# octanis_eps_mcu_shdn.net
KiCad netlist of a schematic drawn in EAGLE
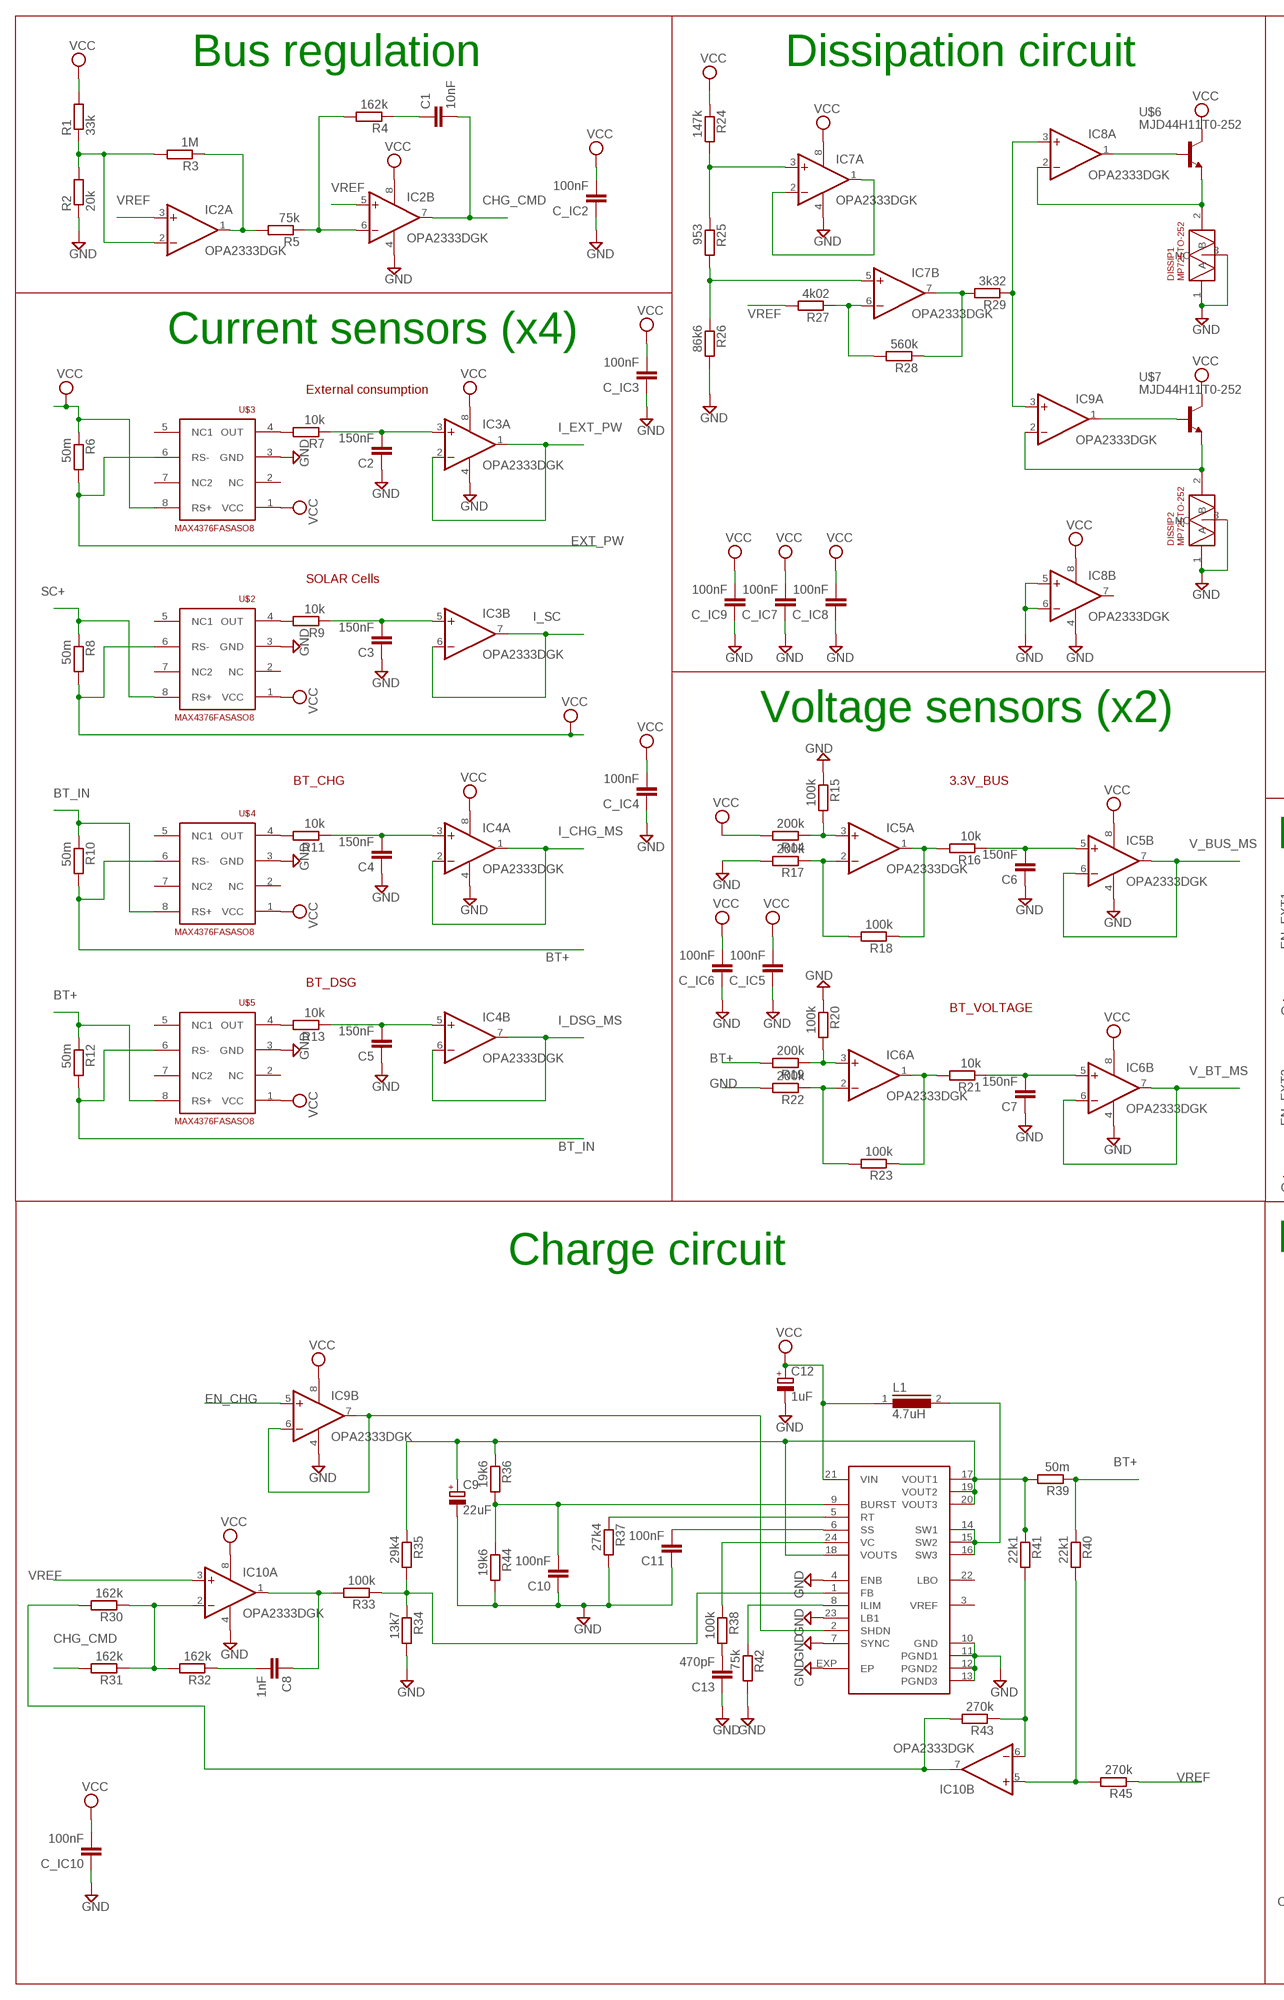
[diagram p0: schematic, sheet 1, part 1 of 2]
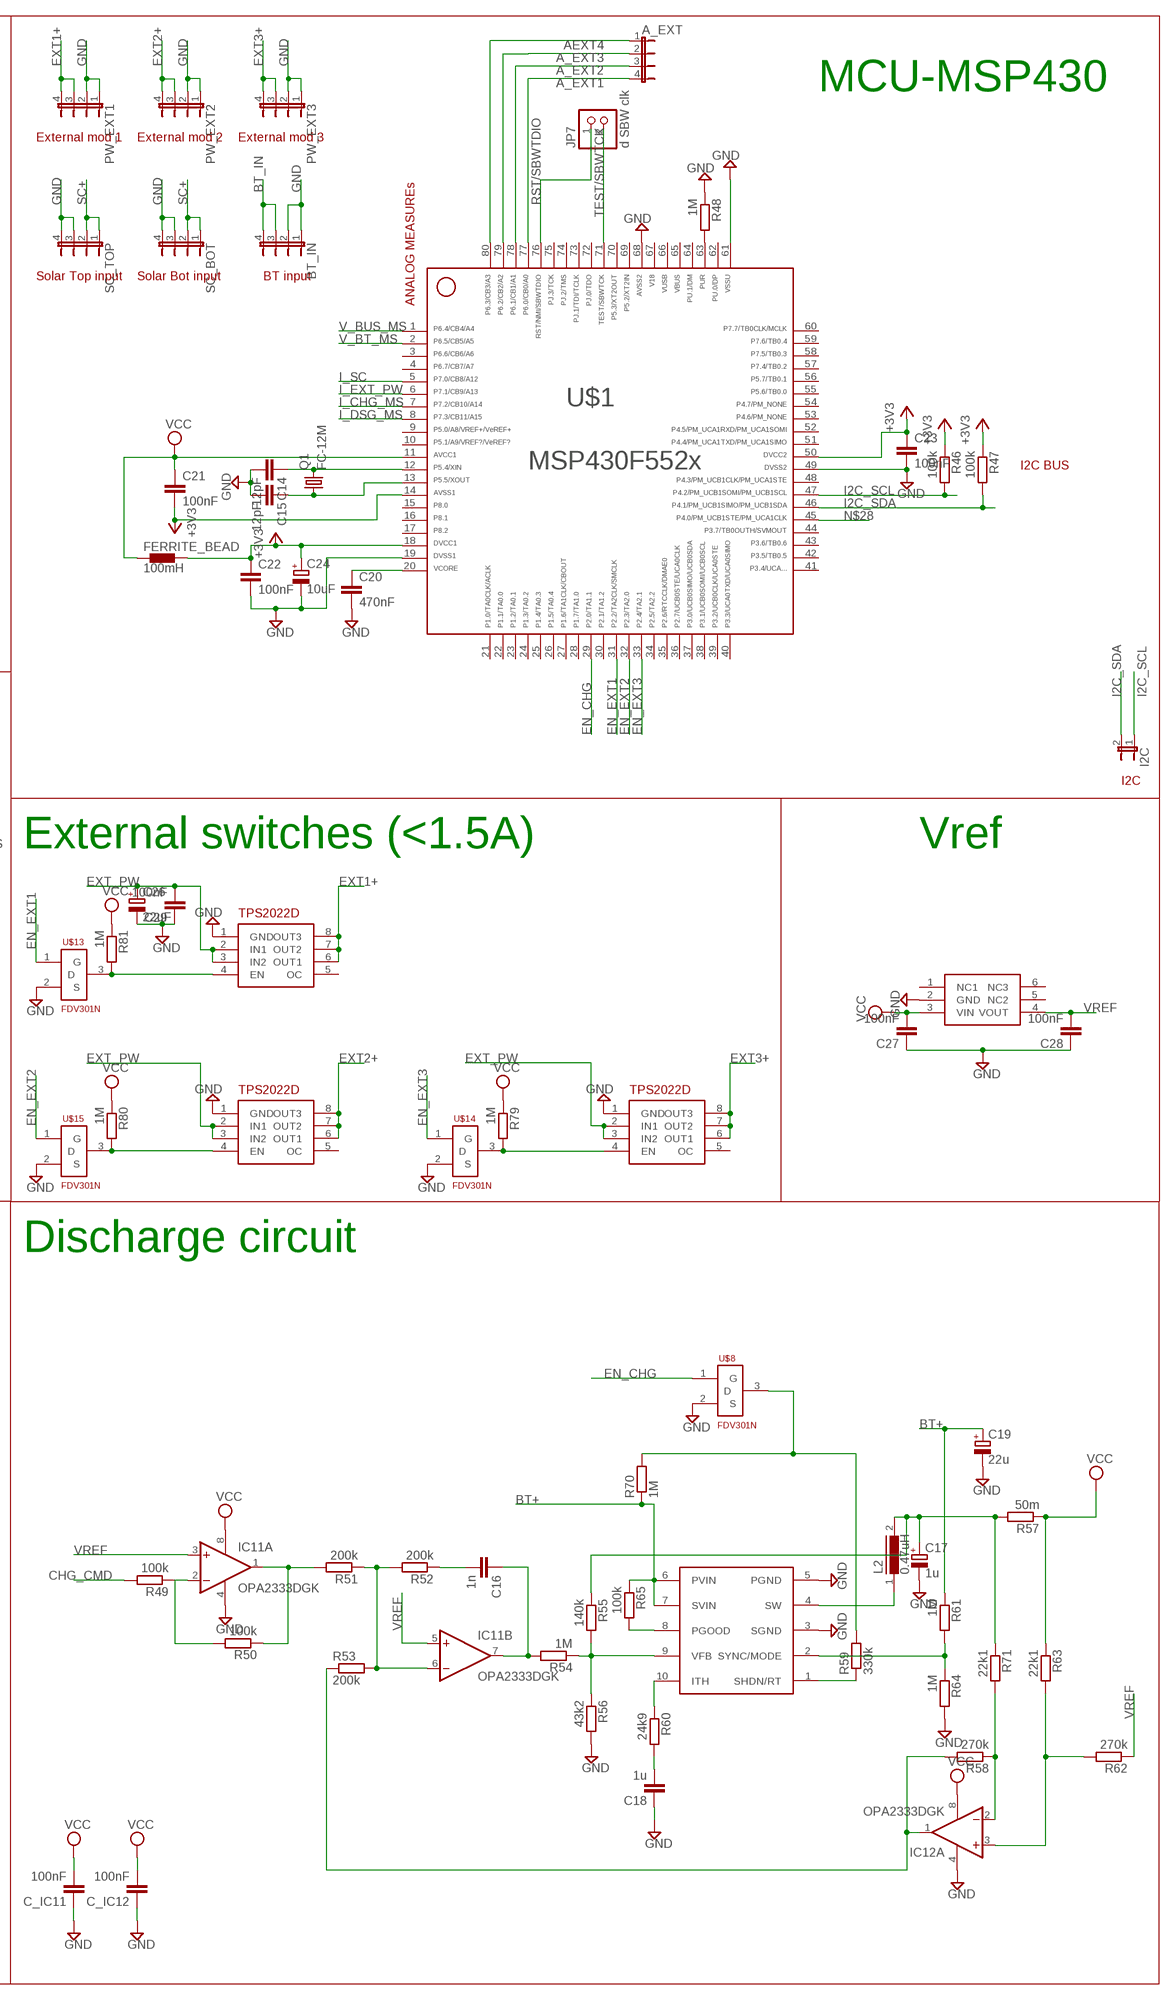
[diagram p1: schematic, sheet 1, part 2 of 2]

(export (version "E")
  (design (tool "Eeschema 10.0.6"))
  (components
    (comp (ref "A_EXT")
      (value "JP4E")
      (footprint "eagle-import:JP4")
      (libsource (lib "eagle-import") (part "JP4E"))
    )
    (comp (ref "BT_IN")
      (value "JP4E")
      (footprint "eagle-import:JP4")
      (libsource (lib "eagle-import") (part "JP4E"))
    )
    (comp (ref "C1")
      (value "10nF")
      (footprint "eagle-import:C0603")
      (libsource (lib "eagle-import") (part "C-EUC0603"))
    )
    (comp (ref "C2")
      (value "150nF")
      (footprint "eagle-import:C0603")
      (libsource (lib "eagle-import") (part "C-EUC0603"))
    )
    (comp (ref "C3")
      (value "150nF")
      (footprint "eagle-import:C0603")
      (libsource (lib "eagle-import") (part "C-EUC0603"))
    )
    (comp (ref "C4")
      (value "150nF")
      (footprint "eagle-import:C0603")
      (libsource (lib "eagle-import") (part "C-EUC0603"))
    )
    (comp (ref "C5")
      (value "150nF")
      (footprint "eagle-import:C0603")
      (libsource (lib "eagle-import") (part "C-EUC0603"))
    )
    (comp (ref "C6")
      (value "150nF")
      (footprint "eagle-import:C0603")
      (libsource (lib "eagle-import") (part "C-EUC0603"))
    )
    (comp (ref "C7")
      (value "150nF")
      (footprint "eagle-import:C0603")
      (libsource (lib "eagle-import") (part "C-EUC0603"))
    )
    (comp (ref "C8")
      (value "1nF")
      (footprint "eagle-import:C0603")
      (libsource (lib "eagle-import") (part "C-EUC0603"))
    )
    (comp (ref "C9")
      (value "22uF")
      (footprint "eagle-import:A_3216-18R")
      (libsource (lib "eagle-import") (part "CPOL-EUA/3216-18R"))
    )
    (comp (ref "C10")
      (value "100nF")
      (footprint "eagle-import:C0603")
      (libsource (lib "eagle-import") (part "C-EUC0603"))
    )
    (comp (ref "C11")
      (value "100nF")
      (footprint "eagle-import:C0603")
      (libsource (lib "eagle-import") (part "C-EUC0603"))
    )
    (comp (ref "C12")
      (value "1uF")
      (footprint "eagle-import:A_3216-18R")
      (libsource (lib "eagle-import") (part "CPOL-EUA/3216-18R"))
    )
    (comp (ref "C13")
      (value "470pF")
      (footprint "eagle-import:C0603")
      (libsource (lib "eagle-import") (part "C-EUC0603"))
    )
    (comp (ref "C14")
      (value "12pF")
      (footprint "eagle-import:C0603")
      (libsource (lib "eagle-import") (part "C-EUC0603"))
    )
    (comp (ref "C15")
      (value "12pF")
      (footprint "eagle-import:C0603")
      (libsource (lib "eagle-import") (part "C-EUC0603"))
    )
    (comp (ref "C16")
      (value "1n")
      (footprint "eagle-import:C0603")
      (libsource (lib "eagle-import") (part "C-EUC0603"))
    )
    (comp (ref "C17")
      (value "1u")
      (footprint "eagle-import:A_3216-18R")
      (libsource (lib "eagle-import") (part "CPOL-EUA/3216-18R"))
    )
    (comp (ref "C18")
      (value "1u")
      (footprint "eagle-import:C0603")
      (libsource (lib "eagle-import") (part "C-EUC0603"))
    )
    (comp (ref "C19")
      (value "22u")
      (footprint "eagle-import:A_3216-18R")
      (libsource (lib "eagle-import") (part "CPOL-EUA/3216-18R"))
    )
    (comp (ref "C20")
      (value "470nF")
      (footprint "eagle-import:C0603")
      (libsource (lib "eagle-import") (part "C-EUC0603"))
    )
    (comp (ref "C21")
      (value "100nF")
      (footprint "eagle-import:C0603")
      (libsource (lib "eagle-import") (part "C-EUC0603"))
    )
    (comp (ref "C22")
      (value "100nF")
      (footprint "eagle-import:C0603")
      (libsource (lib "eagle-import") (part "C-EUC0603"))
    )
    (comp (ref "C23")
      (value "100nF")
      (footprint "eagle-import:C0603")
      (libsource (lib "eagle-import") (part "C-EUC0603"))
    )
    (comp (ref "C24")
      (value "10uF")
      (footprint "eagle-import:A_3216-18R")
      (libsource (lib "eagle-import") (part "CPOL-EUA/3216-18R"))
    )
    (comp (ref "C26")
      (value "22uF")
      (footprint "eagle-import:A_3216-18R")
      (libsource (lib "eagle-import") (part "CPOL-EUA/3216-18R"))
    )
    (comp (ref "C27")
      (value "100nF")
      (footprint "eagle-import:C0603")
      (libsource (lib "eagle-import") (part "C-EUC0603"))
    )
    (comp (ref "C28")
      (value "100nF")
      (footprint "eagle-import:C0603")
      (libsource (lib "eagle-import") (part "C-EUC0603"))
    )
    (comp (ref "C29")
      (value "100nF")
      (footprint "eagle-import:C0603")
      (libsource (lib "eagle-import") (part "C-EUC0603"))
    )
    (comp (ref "C_IC2")
      (value "100nF")
      (footprint "eagle-import:C0603")
      (libsource (lib "eagle-import") (part "C-EUC0603"))
    )
    (comp (ref "C_IC3")
      (value "100nF")
      (footprint "eagle-import:C0603")
      (libsource (lib "eagle-import") (part "C-EUC0603"))
    )
    (comp (ref "C_IC4")
      (value "100nF")
      (footprint "eagle-import:C0603")
      (libsource (lib "eagle-import") (part "C-EUC0603"))
    )
    (comp (ref "C_IC5")
      (value "100nF")
      (footprint "eagle-import:C0603")
      (libsource (lib "eagle-import") (part "C-EUC0603"))
    )
    (comp (ref "C_IC6")
      (value "100nF")
      (footprint "eagle-import:C0603")
      (libsource (lib "eagle-import") (part "C-EUC0603"))
    )
    (comp (ref "C_IC7")
      (value "100nF")
      (footprint "eagle-import:C0603")
      (libsource (lib "eagle-import") (part "C-EUC0603"))
    )
    (comp (ref "C_IC8")
      (value "100nF")
      (footprint "eagle-import:C0603")
      (libsource (lib "eagle-import") (part "C-EUC0603"))
    )
    (comp (ref "C_IC9")
      (value "100nF")
      (footprint "eagle-import:C0603")
      (libsource (lib "eagle-import") (part "C-EUC0603"))
    )
    (comp (ref "C_IC10")
      (value "100nF")
      (footprint "eagle-import:C0603")
      (libsource (lib "eagle-import") (part "C-EUC0603"))
    )
    (comp (ref "C_IC11")
      (value "100nF")
      (footprint "eagle-import:C0603")
      (libsource (lib "eagle-import") (part "C-EUC0603"))
    )
    (comp (ref "C_IC12")
      (value "100nF")
      (footprint "eagle-import:C0603")
      (libsource (lib "eagle-import") (part "C-EUC0603"))
    )
    (comp (ref "DISSIP1")
      (value "MP725TO-252")
      (footprint "eagle-import:TO252")
      (libsource (lib "eagle-import") (part "MP725TO-252"))
    )
    (comp (ref "DISSIP2")
      (value "MP725TO-252")
      (footprint "eagle-import:TO252")
      (libsource (lib "eagle-import") (part "MP725TO-252"))
    )
    (comp (ref "FERRITE_BEAD")
      (value "100mH")
      (footprint "eagle-import:0402")
      (libsource (lib "eagle-import") (part "BLM15HD601SN1"))
    )
    (comp (ref "I2C")
      (value "JP1E")
      (footprint "eagle-import:JP1")
      (libsource (lib "eagle-import") (part "JP1E"))
    )
    (comp (ref "IC2")
      (value "OPA2333DGK")
      (footprint "eagle-import:MSOP08")
      (libsource (lib "eagle-import") (part "OPA2333DGK"))
    )
    (comp (ref "IC3")
      (value "OPA2333DGK")
      (footprint "eagle-import:MSOP08")
      (libsource (lib "eagle-import") (part "OPA2333DGK"))
    )
    (comp (ref "IC4")
      (value "OPA2333DGK")
      (footprint "eagle-import:MSOP08")
      (libsource (lib "eagle-import") (part "OPA2333DGK"))
    )
    (comp (ref "IC5")
      (value "OPA2333DGK")
      (footprint "eagle-import:MSOP08")
      (libsource (lib "eagle-import") (part "OPA2333DGK"))
    )
    (comp (ref "IC6")
      (value "OPA2333DGK")
      (footprint "eagle-import:MSOP08")
      (libsource (lib "eagle-import") (part "OPA2333DGK"))
    )
    (comp (ref "IC7")
      (value "OPA2333DGK")
      (footprint "eagle-import:MSOP08")
      (libsource (lib "eagle-import") (part "OPA2333DGK"))
    )
    (comp (ref "IC8")
      (value "OPA2333DGK")
      (footprint "eagle-import:MSOP08")
      (libsource (lib "eagle-import") (part "OPA2333DGK"))
    )
    (comp (ref "IC9")
      (value "OPA2333DGK")
      (footprint "eagle-import:MSOP08")
      (libsource (lib "eagle-import") (part "OPA2333DGK"))
    )
    (comp (ref "IC10")
      (value "OPA2333DGK")
      (footprint "eagle-import:MSOP08")
      (libsource (lib "eagle-import") (part "OPA2333DGK"))
    )
    (comp (ref "IC11")
      (value "OPA2333DGK")
      (footprint "eagle-import:MSOP08")
      (libsource (lib "eagle-import") (part "OPA2333DGK"))
    )
    (comp (ref "IC12")
      (value "OPA2333DGK")
      (footprint "eagle-import:MSOP08")
      (libsource (lib "eagle-import") (part "OPA2333DGK"))
    )
    (comp (ref "JP7")
      (value "d SBW clk")
      (footprint "eagle-import:1X02")
      (libsource (lib "eagle-import") (part "PINHD-1X2"))
    )
    (comp (ref "L1")
      (value "4.7uH")
      (footprint "eagle-import:DR73")
      (libsource (lib "eagle-import") (part "DR73"))
    )
    (comp (ref "L2")
      (value "0.47uH")
      (footprint "eagle-import:DR73")
      (libsource (lib "eagle-import") (part "DR73"))
    )
    (comp (ref "LTC3411")
      (value "LT3411")
      (footprint "eagle-import:MSOP10")
      (libsource (lib "eagle-import") (part "LT3411"))
    )
    (comp (ref "PW_EXT1")
      (value "JP4E")
      (footprint "eagle-import:JP4")
      (libsource (lib "eagle-import") (part "JP4E"))
    )
    (comp (ref "PW_EXT2")
      (value "JP4E")
      (footprint "eagle-import:JP4")
      (libsource (lib "eagle-import") (part "JP4E"))
    )
    (comp (ref "PW_EXT3")
      (value "JP4E")
      (footprint "eagle-import:JP4")
      (libsource (lib "eagle-import") (part "JP4E"))
    )
    (comp (ref "Q1")
      (value "FC-12M")
      (footprint "eagle-import:FC-12M")
      (libsource (lib "eagle-import") (part "FC-12M"))
    )
    (comp (ref "R1")
      (value "33k")
      (footprint "eagle-import:R0603")
      (libsource (lib "eagle-import") (part "R-EU_R0603"))
    )
    (comp (ref "R2")
      (value "20k")
      (footprint "eagle-import:R0603")
      (libsource (lib "eagle-import") (part "R-EU_R0603"))
    )
    (comp (ref "R3")
      (value "1M")
      (footprint "eagle-import:R0603")
      (libsource (lib "eagle-import") (part "R-EU_R0603"))
    )
    (comp (ref "R4")
      (value "162k")
      (footprint "eagle-import:R0603")
      (libsource (lib "eagle-import") (part "R-EU_R0603"))
    )
    (comp (ref "R5")
      (value "75k")
      (footprint "eagle-import:R0603")
      (libsource (lib "eagle-import") (part "R-EU_R0603"))
    )
    (comp (ref "R6")
      (value "50m")
      (footprint "eagle-import:R1206")
      (libsource (lib "eagle-import") (part "R-EU_R1206"))
    )
    (comp (ref "R7")
      (value "10k")
      (footprint "eagle-import:R0603")
      (libsource (lib "eagle-import") (part "R-EU_R0603"))
    )
    (comp (ref "R8")
      (value "50m")
      (footprint "eagle-import:R1206")
      (libsource (lib "eagle-import") (part "R-EU_R1206"))
    )
    (comp (ref "R9")
      (value "10k")
      (footprint "eagle-import:R0603")
      (libsource (lib "eagle-import") (part "R-EU_R0603"))
    )
    (comp (ref "R10")
      (value "50m")
      (footprint "eagle-import:R1206")
      (libsource (lib "eagle-import") (part "R-EU_R1206"))
    )
    (comp (ref "R11")
      (value "10k")
      (footprint "eagle-import:R0603")
      (libsource (lib "eagle-import") (part "R-EU_R0603"))
    )
    (comp (ref "R12")
      (value "50m")
      (footprint "eagle-import:R1206")
      (libsource (lib "eagle-import") (part "R-EU_R1206"))
    )
    (comp (ref "R13")
      (value "10k")
      (footprint "eagle-import:R0603")
      (libsource (lib "eagle-import") (part "R-EU_R0603"))
    )
    (comp (ref "R14")
      (value "200k")
      (footprint "eagle-import:R0603")
      (libsource (lib "eagle-import") (part "R-EU_R0603"))
    )
    (comp (ref "R15")
      (value "100k")
      (footprint "eagle-import:R0603")
      (libsource (lib "eagle-import") (part "R-EU_R0603"))
    )
    (comp (ref "R16")
      (value "10k")
      (footprint "eagle-import:R0603")
      (libsource (lib "eagle-import") (part "R-EU_R0603"))
    )
    (comp (ref "R17")
      (value "200k")
      (footprint "eagle-import:R0603")
      (libsource (lib "eagle-import") (part "R-EU_R0603"))
    )
    (comp (ref "R18")
      (value "100k")
      (footprint "eagle-import:R0603")
      (libsource (lib "eagle-import") (part "R-EU_R0603"))
    )
    (comp (ref "R19")
      (value "200k")
      (footprint "eagle-import:R0603")
      (libsource (lib "eagle-import") (part "R-EU_R0603"))
    )
    (comp (ref "R20")
      (value "100k")
      (footprint "eagle-import:R0603")
      (libsource (lib "eagle-import") (part "R-EU_R0603"))
    )
    (comp (ref "R21")
      (value "10k")
      (footprint "eagle-import:R0603")
      (libsource (lib "eagle-import") (part "R-EU_R0603"))
    )
    (comp (ref "R22")
      (value "200k")
      (footprint "eagle-import:R0603")
      (libsource (lib "eagle-import") (part "R-EU_R0603"))
    )
    (comp (ref "R23")
      (value "100k")
      (footprint "eagle-import:R0603")
      (libsource (lib "eagle-import") (part "R-EU_R0603"))
    )
    (comp (ref "R24")
      (value "147k")
      (footprint "eagle-import:R0603")
      (libsource (lib "eagle-import") (part "R-EU_R0603"))
    )
    (comp (ref "R25")
      (value "953")
      (footprint "eagle-import:R0603")
      (libsource (lib "eagle-import") (part "R-EU_R0603"))
    )
    (comp (ref "R26")
      (value "86k6")
      (footprint "eagle-import:R0603")
      (libsource (lib "eagle-import") (part "R-EU_R0603"))
    )
    (comp (ref "R27")
      (value "4k02")
      (footprint "eagle-import:R0603")
      (libsource (lib "eagle-import") (part "R-EU_R0603"))
    )
    (comp (ref "R28")
      (value "560k")
      (footprint "eagle-import:R0603")
      (libsource (lib "eagle-import") (part "R-EU_R0603"))
    )
    (comp (ref "R29")
      (value "3k32")
      (footprint "eagle-import:R0603")
      (libsource (lib "eagle-import") (part "R-EU_R0603"))
    )
    (comp (ref "R30")
      (value "162k")
      (footprint "eagle-import:R0603")
      (libsource (lib "eagle-import") (part "R-EU_R0603"))
    )
    (comp (ref "R31")
      (value "162k")
      (footprint "eagle-import:R0603")
      (libsource (lib "eagle-import") (part "R-EU_R0603"))
    )
    (comp (ref "R32")
      (value "162k")
      (footprint "eagle-import:R0603")
      (libsource (lib "eagle-import") (part "R-EU_R0603"))
    )
    (comp (ref "R33")
      (value "100k")
      (footprint "eagle-import:R0603")
      (libsource (lib "eagle-import") (part "R-EU_R0603"))
    )
    (comp (ref "R34")
      (value "13k7")
      (footprint "eagle-import:R0603")
      (libsource (lib "eagle-import") (part "R-EU_R0603"))
    )
    (comp (ref "R35")
      (value "29k4")
      (footprint "eagle-import:R0603")
      (libsource (lib "eagle-import") (part "R-EU_R0603"))
    )
    (comp (ref "R36")
      (value "19k6")
      (footprint "eagle-import:R0603")
      (libsource (lib "eagle-import") (part "R-EU_R0603"))
    )
    (comp (ref "R37")
      (value "27k4")
      (footprint "eagle-import:R0603")
      (libsource (lib "eagle-import") (part "R-EU_R0603"))
    )
    (comp (ref "R38")
      (value "100k")
      (footprint "eagle-import:R0603")
      (libsource (lib "eagle-import") (part "R-EU_R0603"))
    )
    (comp (ref "R39")
      (value "50m")
      (footprint "eagle-import:R1206")
      (libsource (lib "eagle-import") (part "R-EU_R1206"))
    )
    (comp (ref "R40")
      (value "22k1")
      (footprint "eagle-import:R0603")
      (libsource (lib "eagle-import") (part "R-EU_R0603"))
    )
    (comp (ref "R41")
      (value "22k1")
      (footprint "eagle-import:R0603")
      (libsource (lib "eagle-import") (part "R-EU_R0603"))
    )
    (comp (ref "R42")
      (value "75k")
      (footprint "eagle-import:R0603")
      (libsource (lib "eagle-import") (part "R-EU_R0603"))
    )
    (comp (ref "R43")
      (value "270k")
      (footprint "eagle-import:R0603")
      (libsource (lib "eagle-import") (part "R-EU_R0603"))
    )
    (comp (ref "R44")
      (value "19k6")
      (footprint "eagle-import:R0603")
      (libsource (lib "eagle-import") (part "R-EU_R0603"))
    )
    (comp (ref "R45")
      (value "270k")
      (footprint "eagle-import:R0603")
      (libsource (lib "eagle-import") (part "R-EU_R0603"))
    )
    (comp (ref "R46")
      (value "100k")
      (footprint "eagle-import:R0603")
      (libsource (lib "eagle-import") (part "R-EU_R0603"))
    )
    (comp (ref "R47")
      (value "100k")
      (footprint "eagle-import:R0603")
      (libsource (lib "eagle-import") (part "R-EU_R0603"))
    )
    (comp (ref "R48")
      (value "1M")
      (footprint "eagle-import:R0603")
      (libsource (lib "eagle-import") (part "R-EU_R0603"))
    )
    (comp (ref "R49")
      (value "100k")
      (footprint "eagle-import:R0603")
      (libsource (lib "eagle-import") (part "R-EU_R0603"))
    )
    (comp (ref "R50")
      (value "100k")
      (footprint "eagle-import:R0603")
      (libsource (lib "eagle-import") (part "R-EU_R0603"))
    )
    (comp (ref "R51")
      (value "200k")
      (footprint "eagle-import:R0603")
      (libsource (lib "eagle-import") (part "R-EU_R0603"))
    )
    (comp (ref "R52")
      (value "200k")
      (footprint "eagle-import:R0603")
      (libsource (lib "eagle-import") (part "R-EU_R0603"))
    )
    (comp (ref "R53")
      (value "200k")
      (footprint "eagle-import:R0603")
      (libsource (lib "eagle-import") (part "R-EU_R0603"))
    )
    (comp (ref "R54")
      (value "1M")
      (footprint "eagle-import:R0603")
      (libsource (lib "eagle-import") (part "R-EU_R0603"))
    )
    (comp (ref "R55")
      (value "140k")
      (footprint "eagle-import:R0603")
      (libsource (lib "eagle-import") (part "R-EU_R0603"))
    )
    (comp (ref "R56")
      (value "43k2")
      (footprint "eagle-import:R0603")
      (libsource (lib "eagle-import") (part "R-EU_R0603"))
    )
    (comp (ref "R57")
      (value "50m")
      (footprint "eagle-import:R1206")
      (libsource (lib "eagle-import") (part "R-EU_R1206"))
    )
    (comp (ref "R58")
      (value "270k")
      (footprint "eagle-import:R0603")
      (libsource (lib "eagle-import") (part "R-EU_R0603"))
    )
    (comp (ref "R59")
      (value "330k")
      (footprint "eagle-import:R0603")
      (libsource (lib "eagle-import") (part "R-EU_R0603"))
    )
    (comp (ref "R60")
      (value "24k9")
      (footprint "eagle-import:R0603")
      (libsource (lib "eagle-import") (part "R-EU_R0603"))
    )
    (comp (ref "R61")
      (value "1M")
      (footprint "eagle-import:R0603")
      (libsource (lib "eagle-import") (part "R-EU_R0603"))
    )
    (comp (ref "R62")
      (value "270k")
      (footprint "eagle-import:R0603")
      (libsource (lib "eagle-import") (part "R-EU_R0603"))
    )
    (comp (ref "R63")
      (value "22k1")
      (footprint "eagle-import:R0603")
      (libsource (lib "eagle-import") (part "R-EU_R0603"))
    )
    (comp (ref "R64")
      (value "1M")
      (footprint "eagle-import:R0603")
      (libsource (lib "eagle-import") (part "R-EU_R0603"))
    )
    (comp (ref "R65")
      (value "100k")
      (footprint "eagle-import:R0603")
      (libsource (lib "eagle-import") (part "R-EU_R0603"))
    )
    (comp (ref "R70")
      (value "1M")
      (footprint "eagle-import:R0603")
      (libsource (lib "eagle-import") (part "R-EU_R0603"))
    )
    (comp (ref "R71")
      (value "22k1")
      (footprint "eagle-import:R0603")
      (libsource (lib "eagle-import") (part "R-EU_R0603"))
    )
    (comp (ref "R79")
      (value "1M")
      (footprint "eagle-import:R0603")
      (libsource (lib "eagle-import") (part "R-EU_R0603"))
    )
    (comp (ref "R80")
      (value "1M")
      (footprint "eagle-import:R0603")
      (libsource (lib "eagle-import") (part "R-EU_R0603"))
    )
    (comp (ref "R81")
      (value "1M")
      (footprint "eagle-import:R0603")
      (libsource (lib "eagle-import") (part "R-EU_R0603"))
    )
    (comp (ref "SC_BOT")
      (value "JP4E")
      (footprint "eagle-import:JP4")
      (libsource (lib "eagle-import") (part "JP4E"))
    )
    (comp (ref "SC_TOP")
      (value "JP4E")
      (footprint "eagle-import:JP4")
      (libsource (lib "eagle-import") (part "JP4E"))
    )
    (comp (ref "U$1")
      (value "F552X---PN80")
      (footprint "eagle-import:PN80")
      (libsource (lib "eagle-import") (part "F552X---PN80"))
    )
    (comp (ref "U$2")
      (value "MAX4376FASASO8")
      (footprint "eagle-import:SO8")
      (libsource (lib "eagle-import") (part "MAX4376FASASO8"))
    )
    (comp (ref "U$3")
      (value "MAX4376FASASO8")
      (footprint "eagle-import:SO8")
      (libsource (lib "eagle-import") (part "MAX4376FASASO8"))
    )
    (comp (ref "U$4")
      (value "MAX4376FASASO8")
      (footprint "eagle-import:SO8")
      (libsource (lib "eagle-import") (part "MAX4376FASASO8"))
    )
    (comp (ref "U$5")
      (value "MAX4376FASASO8")
      (footprint "eagle-import:SO8")
      (libsource (lib "eagle-import") (part "MAX4376FASASO8"))
    )
    (comp (ref "U$6")
      (value "MJD44H11T0-252")
      (footprint "eagle-import:TO252")
      (libsource (lib "eagle-import") (part "MJD44H11T0-252"))
    )
    (comp (ref "U$7")
      (value "MJD44H11T0-252")
      (footprint "eagle-import:TO252")
      (libsource (lib "eagle-import") (part "MJD44H11T0-252"))
    )
    (comp (ref "U$8")
      (value "FDV301N")
      (footprint "eagle-import:SOT23")
      (libsource (lib "eagle-import") (part "FDV301N"))
    )
    (comp (ref "U$11")
      (value "LTC3421")
      (footprint "eagle-import:QFN24")
      (libsource (lib "eagle-import") (part "LTC3421"))
    )
    (comp (ref "U$13")
      (value "FDV301N")
      (footprint "eagle-import:SOT23")
      (libsource (lib "eagle-import") (part "FDV301N"))
    )
    (comp (ref "U$14")
      (value "FDV301N")
      (footprint "eagle-import:SOT23")
      (libsource (lib "eagle-import") (part "FDV301N"))
    )
    (comp (ref "U$15")
      (value "FDV301N")
      (footprint "eagle-import:SOT23")
      (libsource (lib "eagle-import") (part "FDV301N"))
    )
    (comp (ref "U$16")
      (value "TPS2022D")
      (footprint "eagle-import:SO8")
      (libsource (lib "eagle-import") (part "TPS2022D"))
    )
    (comp (ref "U$17")
      (value "TPS2022D")
      (footprint "eagle-import:SO8")
      (libsource (lib "eagle-import") (part "TPS2022D"))
    )
    (comp (ref "U$18")
      (value "TPS2022D")
      (footprint "eagle-import:SO8")
      (libsource (lib "eagle-import") (part "TPS2022D"))
    )
    (comp (ref "U$19")
      (value "ADR127B")
      (footprint "eagle-import:TSOT23-6")
      (libsource (lib "eagle-import") (part "ADR127B"))
    )
  )
  (nets
    (net (code "1") (name "+3V3") (class "Default")
      (node (ref "C21") (pin "2") (pinfunction "2_2") (pintype "passive"))
      (node (ref "C22") (pin "1") (pinfunction "1_1") (pintype "passive"))
      (node (ref "C23") (pin "1") (pinfunction "1_1") (pintype "passive"))
      (node (ref "C24") (pin "+") (pinfunction "+_+") (pintype "passive"))
      (node (ref "FERRITE_BEAD") (pin "2") (pinfunction "2_2") (pintype "passive"))
      (node (ref "R46") (pin "1") (pinfunction "1_1") (pintype "passive"))
      (node (ref "R47") (pin "1") (pinfunction "1_1") (pintype "passive"))
      (node (ref "U$1") (pin "14") (pinfunction "14_14") (pintype "power_in"))
      (node (ref "U$1") (pin "18") (pinfunction "18_18") (pintype "power_in"))
      (node (ref "U$1") (pin "50") (pinfunction "50_50") (pintype "power_in"))
    )
    (net (code "2") (name "/65") (class "Default")
      (node (ref "U$1") (pin "65") (pinfunction "65_65") (pintype "power_in"))
    )
    (net (code "3") (name "/66") (class "Default")
      (node (ref "U$1") (pin "66") (pinfunction "66_66") (pintype "power_in"))
    )
    (net (code "4") (name "/67") (class "Default")
      (node (ref "U$1") (pin "67") (pinfunction "67_67") (pintype "power_in"))
    )
    (net (code "5") (name "/AEXT4") (class "Default")
      (node (ref "A_EXT") (pin "1") (pinfunction "1_1") (pintype "passive"))
      (node (ref "U$1") (pin "80") (pinfunction "80_80") (pintype "bidirectional"))
    )
    (net (code "6") (name "/A_EXT1") (class "Default")
      (node (ref "A_EXT") (pin "4") (pinfunction "4_4") (pintype "passive"))
      (node (ref "U$1") (pin "77") (pinfunction "77_77") (pintype "bidirectional"))
    )
    (net (code "7") (name "/A_EXT2") (class "Default")
      (node (ref "A_EXT") (pin "3") (pinfunction "3_3") (pintype "passive"))
      (node (ref "U$1") (pin "78") (pinfunction "78_78") (pintype "bidirectional"))
    )
    (net (code "8") (name "/A_EXT3") (class "Default")
      (node (ref "A_EXT") (pin "2") (pinfunction "2_2") (pintype "passive"))
      (node (ref "U$1") (pin "79") (pinfunction "79_79") (pintype "bidirectional"))
    )
    (net (code "9") (name "/BT+") (class "Default")
      (node (ref "C19") (pin "+") (pinfunction "+_+") (pintype "passive"))
      (node (ref "LTC3411") (pin "6") (pinfunction "PVIN_6") (pintype "bidirectional"))
      (node (ref "LTC3411") (pin "7") (pinfunction "SVIN_7") (pintype "bidirectional"))
      (node (ref "R10") (pin "2") (pinfunction "2_2") (pintype "passive"))
      (node (ref "R12") (pin "1") (pinfunction "1_1") (pintype "passive"))
      (node (ref "R19") (pin "2") (pinfunction "2_2") (pintype "passive"))
      (node (ref "R39") (pin "1") (pinfunction "1_1") (pintype "passive"))
      (node (ref "R40") (pin "1") (pinfunction "1_1") (pintype "passive"))
      (node (ref "R61") (pin "1") (pinfunction "1_1") (pintype "passive"))
      (node (ref "R65") (pin "1") (pinfunction "1_1") (pintype "passive"))
      (node (ref "R70") (pin "1") (pinfunction "1_1") (pintype "passive"))
      (node (ref "U$4") (pin "6") (pinfunction "RS-_6") (pintype "bidirectional"))
      (node (ref "U$5") (pin "8") (pinfunction "RS+_8") (pintype "bidirectional"))
    )
    (net (code "10") (name "/BT_IN") (class "Default")
      (node (ref "BT_IN") (pin "3") (pinfunction "3_3") (pintype "passive"))
      (node (ref "BT_IN") (pin "4") (pinfunction "4_4") (pintype "passive"))
      (node (ref "R10") (pin "1") (pinfunction "1_1") (pintype "passive"))
      (node (ref "R12") (pin "2") (pinfunction "2_2") (pintype "passive"))
      (node (ref "U$4") (pin "8") (pinfunction "RS+_8") (pintype "bidirectional"))
      (node (ref "U$5") (pin "6") (pinfunction "RS-_6") (pintype "bidirectional"))
    )
    (net (code "11") (name "/CHG_CMD") (class "Default")
      (node (ref "C1") (pin "2") (pinfunction "2_2") (pintype "passive"))
      (node (ref "IC2") (pin "7") (pinfunction "OUT_7") (pintype "output"))
      (node (ref "R31") (pin "2") (pinfunction "2_2") (pintype "passive"))
      (node (ref "R49") (pin "2") (pinfunction "2_2") (pintype "passive"))
    )
    (net (code "12") (name "/EN_CHG") (class "Default")
      (node (ref "IC9") (pin "5") (pinfunction "+IN_5") (pintype "input"))
      (node (ref "U$1") (pin "29") (pinfunction "29_29") (pintype "bidirectional"))
      (node (ref "U$8") (pin "1") (pinfunction "G_1") (pintype "bidirectional"))
    )
    (net (code "13") (name "/EN_EXT1") (class "Default")
      (node (ref "U$1") (pin "31") (pinfunction "31_31") (pintype "bidirectional"))
      (node (ref "U$13") (pin "1") (pinfunction "G_1") (pintype "bidirectional"))
    )
    (net (code "14") (name "/EN_EXT2") (class "Default")
      (node (ref "U$1") (pin "32") (pinfunction "32_32") (pintype "bidirectional"))
      (node (ref "U$15") (pin "1") (pinfunction "G_1") (pintype "bidirectional"))
    )
    (net (code "15") (name "/EN_EXT3") (class "Default")
      (node (ref "U$1") (pin "33") (pinfunction "33_33") (pintype "bidirectional"))
      (node (ref "U$14") (pin "1") (pinfunction "G_1") (pintype "bidirectional"))
    )
    (net (code "16") (name "/EXT1+") (class "Default")
      (node (ref "PW_EXT1") (pin "3") (pinfunction "3_3") (pintype "passive"))
      (node (ref "PW_EXT1") (pin "4") (pinfunction "4_4") (pintype "passive"))
      (node (ref "U$16") (pin "6") (pinfunction "OUT1_6") (pintype "bidirectional"))
      (node (ref "U$16") (pin "7") (pinfunction "OUT2_7") (pintype "bidirectional"))
      (node (ref "U$16") (pin "8") (pinfunction "OUT3_8") (pintype "bidirectional"))
    )
    (net (code "17") (name "/EXT2+") (class "Default")
      (node (ref "PW_EXT2") (pin "3") (pinfunction "3_3") (pintype "passive"))
      (node (ref "PW_EXT2") (pin "4") (pinfunction "4_4") (pintype "passive"))
      (node (ref "U$17") (pin "6") (pinfunction "OUT1_6") (pintype "bidirectional"))
      (node (ref "U$17") (pin "7") (pinfunction "OUT2_7") (pintype "bidirectional"))
      (node (ref "U$17") (pin "8") (pinfunction "OUT3_8") (pintype "bidirectional"))
    )
    (net (code "18") (name "/EXT3+") (class "Default")
      (node (ref "PW_EXT3") (pin "3") (pinfunction "3_3") (pintype "passive"))
      (node (ref "PW_EXT3") (pin "4") (pinfunction "4_4") (pintype "passive"))
      (node (ref "U$18") (pin "6") (pinfunction "OUT1_6") (pintype "bidirectional"))
      (node (ref "U$18") (pin "7") (pinfunction "OUT2_7") (pintype "bidirectional"))
      (node (ref "U$18") (pin "8") (pinfunction "OUT3_8") (pintype "bidirectional"))
    )
    (net (code "19") (name "/EXT_PW") (class "Default")
      (node (ref "C26") (pin "+") (pinfunction "+_+") (pintype "passive"))
      (node (ref "C29") (pin "2") (pinfunction "2_2") (pintype "passive"))
      (node (ref "R6") (pin "2") (pinfunction "2_2") (pintype "passive"))
      (node (ref "U$16") (pin "2") (pinfunction "IN1_2") (pintype "bidirectional"))
      (node (ref "U$16") (pin "3") (pinfunction "IN2_3") (pintype "bidirectional"))
      (node (ref "U$17") (pin "2") (pinfunction "IN1_2") (pintype "bidirectional"))
      (node (ref "U$17") (pin "3") (pinfunction "IN2_3") (pintype "bidirectional"))
      (node (ref "U$18") (pin "2") (pinfunction "IN1_2") (pintype "bidirectional"))
      (node (ref "U$18") (pin "3") (pinfunction "IN2_3") (pintype "bidirectional"))
      (node (ref "U$3") (pin "6") (pinfunction "RS-_6") (pintype "bidirectional"))
    )
    (net (code "20") (name "/I2C_SCL") (class "Default")
      (node (ref "I2C") (pin "1") (pinfunction "1_1") (pintype "passive"))
      (node (ref "R46") (pin "2") (pinfunction "2_2") (pintype "passive"))
      (node (ref "U$1") (pin "47") (pinfunction "47_47") (pintype "bidirectional"))
    )
    (net (code "21") (name "/I2C_SDA") (class "Default")
      (node (ref "I2C") (pin "2") (pinfunction "2_2") (pintype "passive"))
      (node (ref "R47") (pin "2") (pinfunction "2_2") (pintype "passive"))
      (node (ref "U$1") (pin "46") (pinfunction "46_46") (pintype "bidirectional"))
    )
    (net (code "22") (name "/I_CHG_MS") (class "Default")
      (node (ref "IC4") (pin "1") (pinfunction "OUT_1") (pintype "output"))
      (node (ref "IC4") (pin "2") (pinfunction "-IN_2") (pintype "input"))
      (node (ref "U$1") (pin "7") (pinfunction "7_7") (pintype "bidirectional"))
    )
    (net (code "23") (name "/I_DSG_MS") (class "Default")
      (node (ref "IC4") (pin "6") (pinfunction "-IN_6") (pintype "input"))
      (node (ref "IC4") (pin "7") (pinfunction "OUT_7") (pintype "output"))
      (node (ref "U$1") (pin "8") (pinfunction "8_8") (pintype "bidirectional"))
    )
    (net (code "24") (name "/I_EXT_PW") (class "Default")
      (node (ref "IC3") (pin "1") (pinfunction "OUT_1") (pintype "output"))
      (node (ref "IC3") (pin "2") (pinfunction "-IN_2") (pintype "input"))
      (node (ref "U$1") (pin "6") (pinfunction "6_6") (pintype "bidirectional"))
    )
    (net (code "25") (name "/I_SC") (class "Default")
      (node (ref "IC3") (pin "6") (pinfunction "-IN_6") (pintype "input"))
      (node (ref "IC3") (pin "7") (pinfunction "OUT_7") (pintype "output"))
      (node (ref "U$1") (pin "5") (pinfunction "5_5") (pintype "bidirectional"))
    )
    (net (code "26") (name "/N$28") (class "Default")
      (node (ref "U$1") (pin "45") (pinfunction "45_45") (pintype "bidirectional"))
    )
    (net (code "27") (name "/RST{slash}SBWTDIO") (class "Default")
      (node (ref "JP7") (pin "1") (pinfunction "1_1") (pintype "passive"))
      (node (ref "U$1") (pin "76") (pinfunction "76_76") (pintype "bidirectional"))
    )
    (net (code "28") (name "/SC+") (class "Default")
      (node (ref "R8") (pin "1") (pinfunction "1_1") (pintype "passive"))
      (node (ref "SC_BOT") (pin "1") (pinfunction "1_1") (pintype "passive"))
      (node (ref "SC_BOT") (pin "2") (pinfunction "2_2") (pintype "passive"))
      (node (ref "SC_TOP") (pin "1") (pinfunction "1_1") (pintype "passive"))
      (node (ref "SC_TOP") (pin "2") (pinfunction "2_2") (pintype "passive"))
      (node (ref "U$2") (pin "8") (pinfunction "RS+_8") (pintype "bidirectional"))
    )
    (net (code "29") (name "/TEST{slash}SBWTCK") (class "Default")
      (node (ref "JP7") (pin "2") (pinfunction "2_2") (pintype "passive"))
      (node (ref "U$1") (pin "71") (pinfunction "71_71") (pintype "input"))
    )
    (net (code "30") (name "/VREF") (class "Default")
      (node (ref "C28") (pin "2") (pinfunction "2_2") (pintype "passive"))
      (node (ref "IC10") (pin "3") (pinfunction "+IN_3") (pintype "input"))
      (node (ref "IC11") (pin "3") (pinfunction "+IN_3") (pintype "input"))
      (node (ref "IC11") (pin "5") (pinfunction "+IN_5") (pintype "input"))
      (node (ref "IC2") (pin "3") (pinfunction "+IN_3") (pintype "input"))
      (node (ref "IC2") (pin "5") (pinfunction "+IN_5") (pintype "input"))
      (node (ref "R27") (pin "2") (pinfunction "2_2") (pintype "passive"))
      (node (ref "R45") (pin "1") (pinfunction "1_1") (pintype "passive"))
      (node (ref "R62") (pin "1") (pinfunction "1_1") (pintype "passive"))
      (node (ref "U$19") (pin "4") (pinfunction "VOUT_4") (pintype "bidirectional"))
    )
    (net (code "31") (name "/V_BT_MS") (class "Default")
      (node (ref "IC6") (pin "6") (pinfunction "-IN_6") (pintype "input"))
      (node (ref "IC6") (pin "7") (pinfunction "OUT_7") (pintype "output"))
      (node (ref "U$1") (pin "2") (pinfunction "2_2") (pintype "bidirectional"))
    )
    (net (code "32") (name "/V_BUS_MS") (class "Default")
      (node (ref "IC5") (pin "6") (pinfunction "-IN_6") (pintype "input"))
      (node (ref "IC5") (pin "7") (pinfunction "OUT_7") (pintype "output"))
      (node (ref "U$1") (pin "1") (pinfunction "1_1") (pintype "bidirectional"))
    )
    (net (code "33") (name "GND") (class "Default")
      (node (ref "BT_IN") (pin "1") (pinfunction "1_1") (pintype "passive"))
      (node (ref "BT_IN") (pin "2") (pinfunction "2_2") (pintype "passive"))
      (node (ref "C10") (pin "1") (pinfunction "1_1") (pintype "passive"))
      (node (ref "C11") (pin "1") (pinfunction "1_1") (pintype "passive"))
      (node (ref "C12") (pin "-") (pinfunction "-_-") (pintype "passive"))
      (node (ref "C13") (pin "1") (pinfunction "1_1") (pintype "passive"))
      (node (ref "C14") (pin "2") (pinfunction "2_2") (pintype "passive"))
      (node (ref "C15") (pin "2") (pinfunction "2_2") (pintype "passive"))
      (node (ref "C17") (pin "-") (pinfunction "-_-") (pintype "passive"))
      (node (ref "C18") (pin "1") (pinfunction "1_1") (pintype "passive"))
      (node (ref "C19") (pin "-") (pinfunction "-_-") (pintype "passive"))
      (node (ref "C2") (pin "1") (pinfunction "1_1") (pintype "passive"))
      (node (ref "C20") (pin "2") (pinfunction "2_2") (pintype "passive"))
      (node (ref "C22") (pin "2") (pinfunction "2_2") (pintype "passive"))
      (node (ref "C23") (pin "2") (pinfunction "2_2") (pintype "passive"))
      (node (ref "C24") (pin "-") (pinfunction "-_-") (pintype "passive"))
      (node (ref "C26") (pin "-") (pinfunction "-_-") (pintype "passive"))
      (node (ref "C27") (pin "1") (pinfunction "1_1") (pintype "passive"))
      (node (ref "C28") (pin "1") (pinfunction "1_1") (pintype "passive"))
      (node (ref "C29") (pin "1") (pinfunction "1_1") (pintype "passive"))
      (node (ref "C3") (pin "1") (pinfunction "1_1") (pintype "passive"))
      (node (ref "C4") (pin "1") (pinfunction "1_1") (pintype "passive"))
      (node (ref "C5") (pin "1") (pinfunction "1_1") (pintype "passive"))
      (node (ref "C6") (pin "1") (pinfunction "1_1") (pintype "passive"))
      (node (ref "C7") (pin "1") (pinfunction "1_1") (pintype "passive"))
      (node (ref "C9") (pin "-") (pinfunction "-_-") (pintype "passive"))
      (node (ref "C_IC10") (pin "1") (pinfunction "1_1") (pintype "passive"))
      (node (ref "C_IC11") (pin "1") (pinfunction "1_1") (pintype "passive"))
      (node (ref "C_IC12") (pin "1") (pinfunction "1_1") (pintype "passive"))
      (node (ref "C_IC2") (pin "1") (pinfunction "1_1") (pintype "passive"))
      (node (ref "C_IC3") (pin "1") (pinfunction "1_1") (pintype "passive"))
      (node (ref "C_IC4") (pin "1") (pinfunction "1_1") (pintype "passive"))
      (node (ref "C_IC5") (pin "1") (pinfunction "1_1") (pintype "passive"))
      (node (ref "C_IC6") (pin "1") (pinfunction "1_1") (pintype "passive"))
      (node (ref "C_IC7") (pin "1") (pinfunction "1_1") (pintype "passive"))
      (node (ref "C_IC8") (pin "1") (pinfunction "1_1") (pintype "passive"))
      (node (ref "C_IC9") (pin "1") (pinfunction "1_1") (pintype "passive"))
      (node (ref "DISSIP1") (pin "1") (pinfunction "A_1") (pintype "bidirectional"))
      (node (ref "DISSIP1") (pin "3") (pinfunction "NC_3") (pintype "bidirectional"))
      (node (ref "DISSIP2") (pin "1") (pinfunction "A_1") (pintype "bidirectional"))
      (node (ref "DISSIP2") (pin "3") (pinfunction "NC_3") (pintype "bidirectional"))
      (node (ref "IC10") (pin "4") (pinfunction "V-_4") (pintype "power_in"))
      (node (ref "IC11") (pin "4") (pinfunction "V-_4") (pintype "power_in"))
      (node (ref "IC12") (pin "4") (pinfunction "V-_4") (pintype "power_in"))
      (node (ref "IC2") (pin "4") (pinfunction "V-_4") (pintype "power_in"))
      (node (ref "IC3") (pin "4") (pinfunction "V-_4") (pintype "power_in"))
      (node (ref "IC4") (pin "4") (pinfunction "V-_4") (pintype "power_in"))
      (node (ref "IC5") (pin "4") (pinfunction "V-_4") (pintype "power_in"))
      (node (ref "IC6") (pin "4") (pinfunction "V-_4") (pintype "power_in"))
      (node (ref "IC7") (pin "4") (pinfunction "V-_4") (pintype "power_in"))
      (node (ref "IC8") (pin "4") (pinfunction "V-_4") (pintype "power_in"))
      (node (ref "IC8") (pin "5") (pinfunction "+IN_5") (pintype "input"))
      (node (ref "IC8") (pin "6") (pinfunction "-IN_6") (pintype "input"))
      (node (ref "IC9") (pin "4") (pinfunction "V-_4") (pintype "power_in"))
      (node (ref "LTC3411") (pin "3") (pinfunction "SGND_3") (pintype "bidirectional"))
      (node (ref "LTC3411") (pin "5") (pinfunction "PGND_5") (pintype "bidirectional"))
      (node (ref "PW_EXT1") (pin "1") (pinfunction "1_1") (pintype "passive"))
      (node (ref "PW_EXT1") (pin "2") (pinfunction "2_2") (pintype "passive"))
      (node (ref "PW_EXT2") (pin "1") (pinfunction "1_1") (pintype "passive"))
      (node (ref "PW_EXT2") (pin "2") (pinfunction "2_2") (pintype "passive"))
      (node (ref "PW_EXT3") (pin "1") (pinfunction "1_1") (pintype "passive"))
      (node (ref "PW_EXT3") (pin "2") (pinfunction "2_2") (pintype "passive"))
      (node (ref "R15") (pin "1") (pinfunction "1_1") (pintype "passive"))
      (node (ref "R17") (pin "2") (pinfunction "2_2") (pintype "passive"))
      (node (ref "R2") (pin "1") (pinfunction "1_1") (pintype "passive"))
      (node (ref "R20") (pin "1") (pinfunction "1_1") (pintype "passive"))
      (node (ref "R22") (pin "2") (pinfunction "2_2") (pintype "passive"))
      (node (ref "R26") (pin "2") (pinfunction "2_2") (pintype "passive"))
      (node (ref "R34") (pin "2") (pinfunction "2_2") (pintype "passive"))
      (node (ref "R37") (pin "2") (pinfunction "2_2") (pintype "passive"))
      (node (ref "R42") (pin "2") (pinfunction "2_2") (pintype "passive"))
      (node (ref "R44") (pin "2") (pinfunction "2_2") (pintype "passive"))
      (node (ref "R48") (pin "1") (pinfunction "1_1") (pintype "passive"))
      (node (ref "R56") (pin "2") (pinfunction "2_2") (pintype "passive"))
      (node (ref "R64") (pin "2") (pinfunction "2_2") (pintype "passive"))
      (node (ref "SC_BOT") (pin "3") (pinfunction "3_3") (pintype "passive"))
      (node (ref "SC_BOT") (pin "4") (pinfunction "4_4") (pintype "passive"))
      (node (ref "SC_TOP") (pin "3") (pinfunction "3_3") (pintype "passive"))
      (node (ref "SC_TOP") (pin "4") (pinfunction "4_4") (pintype "passive"))
      (node (ref "U$1") (pin "19") (pinfunction "19_19") (pintype "power_in"))
      (node (ref "U$1") (pin "49") (pinfunction "49_49") (pintype "power_in"))
      (node (ref "U$1") (pin "61") (pinfunction "61_61") (pintype "power_in"))
      (node (ref "U$1") (pin "68") (pinfunction "68_68") (pintype "power_in"))
      (node (ref "U$11") (pin "10") (pinfunction "GND_10") (pintype "bidirectional"))
      (node (ref "U$11") (pin "11") (pinfunction "PGND1_11") (pintype "bidirectional"))
      (node (ref "U$11") (pin "12") (pinfunction "PGND2_12") (pintype "bidirectional"))
      (node (ref "U$11") (pin "13") (pinfunction "PGND3_13") (pintype "bidirectional"))
      (node (ref "U$11") (pin "23") (pinfunction "LB1_23") (pintype "bidirectional"))
      (node (ref "U$11") (pin "4") (pinfunction "ENB_4") (pintype "bidirectional"))
      (node (ref "U$11") (pin "7") (pinfunction "SYNC_7") (pintype "bidirectional"))
      (node (ref "U$11") (pin "EXP") (pinfunction "EP_EXP") (pintype "bidirectional"))
      (node (ref "U$13") (pin "2") (pinfunction "S_2") (pintype "bidirectional"))
      (node (ref "U$14") (pin "2") (pinfunction "S_2") (pintype "bidirectional"))
      (node (ref "U$15") (pin "2") (pinfunction "S_2") (pintype "bidirectional"))
      (node (ref "U$16") (pin "1") (pinfunction "GND_1") (pintype "bidirectional"))
      (node (ref "U$17") (pin "1") (pinfunction "GND_1") (pintype "bidirectional"))
      (node (ref "U$18") (pin "1") (pinfunction "GND_1") (pintype "bidirectional"))
      (node (ref "U$19") (pin "2") (pinfunction "GND_2") (pintype "bidirectional"))
      (node (ref "U$2") (pin "3") (pinfunction "GND_3") (pintype "bidirectional"))
      (node (ref "U$3") (pin "3") (pinfunction "GND_3") (pintype "bidirectional"))
      (node (ref "U$4") (pin "3") (pinfunction "GND_3") (pintype "bidirectional"))
      (node (ref "U$5") (pin "3") (pinfunction "GND_3") (pintype "bidirectional"))
      (node (ref "U$8") (pin "2") (pinfunction "S_2") (pintype "bidirectional"))
    )
    (net (code "34") (name "Net-(C1-Pad1)") (class "Default")
      (node (ref "C1") (pin "1") (pinfunction "1_1") (pintype "passive"))
      (node (ref "R4") (pin "1") (pinfunction "1_1") (pintype "passive"))
    )
    (net (code "35") (name "Net-(C8-Pad2)") (class "Default")
      (node (ref "C8") (pin "2") (pinfunction "2_2") (pintype "passive"))
      (node (ref "R32") (pin "1") (pinfunction "1_1") (pintype "passive"))
    )
    (net (code "36") (name "Net-(C13-Pad2)") (class "Default")
      (node (ref "C13") (pin "2") (pinfunction "2_2") (pintype "passive"))
      (node (ref "R38") (pin "2") (pinfunction "2_2") (pintype "passive"))
    )
    (net (code "37") (name "Net-(C14-Pad1)") (class "Default")
      (node (ref "C14") (pin "1") (pinfunction "1_1") (pintype "passive"))
      (node (ref "Q1") (pin "2") (pinfunction "2_2") (pintype "passive"))
      (node (ref "U$1") (pin "12") (pinfunction "12_12") (pintype "bidirectional"))
    )
    (net (code "38") (name "Net-(C15-Pad1)") (class "Default")
      (node (ref "C15") (pin "1") (pinfunction "1_1") (pintype "passive"))
      (node (ref "Q1") (pin "1") (pinfunction "1_1") (pintype "passive"))
      (node (ref "U$1") (pin "13") (pinfunction "13_13") (pintype "bidirectional"))
    )
    (net (code "39") (name "Net-(C16-Pad2)") (class "Default")
      (node (ref "C16") (pin "2") (pinfunction "2_2") (pintype "passive"))
      (node (ref "R52") (pin "1") (pinfunction "1_1") (pintype "passive"))
    )
    (net (code "40") (name "Net-(C17-Pad+)") (class "Default")
      (node (ref "C17") (pin "+") (pinfunction "+_+") (pintype "passive"))
      (node (ref "L2") (pin "2") (pinfunction "2_2") (pintype "passive"))
      (node (ref "R55") (pin "1") (pinfunction "1_1") (pintype "passive"))
      (node (ref "R57") (pin "2") (pinfunction "2_2") (pintype "passive"))
      (node (ref "R71") (pin "1") (pinfunction "1_1") (pintype "passive"))
    )
    (net (code "41") (name "Net-(C18-Pad2)") (class "Default")
      (node (ref "C18") (pin "2") (pinfunction "2_2") (pintype "passive"))
      (node (ref "R60") (pin "2") (pinfunction "2_2") (pintype "passive"))
    )
    (net (code "42") (name "Net-(C20-Pad1)") (class "Default")
      (node (ref "C20") (pin "1") (pinfunction "1_1") (pintype "passive"))
      (node (ref "U$1") (pin "20") (pinfunction "20_20") (pintype "power_in"))
    )
    (net (code "43") (name "Net-(DISSIP1-B)") (class "Default")
      (node (ref "DISSIP1") (pin "2") (pinfunction "B_2") (pintype "bidirectional"))
      (node (ref "IC8") (pin "2") (pinfunction "-IN_2") (pintype "input"))
      (node (ref "U$6") (pin "3") (pinfunction "E_3") (pintype "passive"))
    )
    (net (code "44") (name "Net-(DISSIP2-B)") (class "Default")
      (node (ref "DISSIP2") (pin "2") (pinfunction "B_2") (pintype "bidirectional"))
      (node (ref "IC9") (pin "2") (pinfunction "-IN_2") (pintype "input"))
      (node (ref "U$7") (pin "3") (pinfunction "E_3") (pintype "passive"))
    )
    (net (code "45") (name "Net-(IC2A--IN)") (class "Default")
      (node (ref "IC2") (pin "2") (pinfunction "-IN_2") (pintype "input"))
      (node (ref "R1") (pin "1") (pinfunction "1_1") (pintype "passive"))
      (node (ref "R2") (pin "2") (pinfunction "2_2") (pintype "passive"))
      (node (ref "R3") (pin "2") (pinfunction "2_2") (pintype "passive"))
    )
    (net (code "46") (name "Net-(IC2A-OUT)") (class "Default")
      (node (ref "IC2") (pin "1") (pinfunction "OUT_1") (pintype "output"))
      (node (ref "R3") (pin "1") (pinfunction "1_1") (pintype "passive"))
      (node (ref "R5") (pin "2") (pinfunction "2_2") (pintype "passive"))
    )
    (net (code "47") (name "Net-(IC2B--IN)") (class "Default")
      (node (ref "IC2") (pin "6") (pinfunction "-IN_6") (pintype "input"))
      (node (ref "R4") (pin "2") (pinfunction "2_2") (pintype "passive"))
      (node (ref "R5") (pin "1") (pinfunction "1_1") (pintype "passive"))
    )
    (net (code "48") (name "Net-(IC3A-+IN)") (class "Default")
      (node (ref "C2") (pin "2") (pinfunction "2_2") (pintype "passive"))
      (node (ref "IC3") (pin "3") (pinfunction "+IN_3") (pintype "input"))
      (node (ref "R7") (pin "1") (pinfunction "1_1") (pintype "passive"))
    )
    (net (code "49") (name "Net-(IC3B-+IN)") (class "Default")
      (node (ref "C3") (pin "2") (pinfunction "2_2") (pintype "passive"))
      (node (ref "IC3") (pin "5") (pinfunction "+IN_5") (pintype "input"))
      (node (ref "R9") (pin "1") (pinfunction "1_1") (pintype "passive"))
    )
    (net (code "50") (name "Net-(IC4A-+IN)") (class "Default")
      (node (ref "C4") (pin "2") (pinfunction "2_2") (pintype "passive"))
      (node (ref "IC4") (pin "3") (pinfunction "+IN_3") (pintype "input"))
      (node (ref "R11") (pin "1") (pinfunction "1_1") (pintype "passive"))
    )
    (net (code "51") (name "Net-(IC4B-+IN)") (class "Default")
      (node (ref "C5") (pin "2") (pinfunction "2_2") (pintype "passive"))
      (node (ref "IC4") (pin "5") (pinfunction "+IN_5") (pintype "input"))
      (node (ref "R13") (pin "1") (pinfunction "1_1") (pintype "passive"))
    )
    (net (code "52") (name "Net-(IC5A-+IN)") (class "Default")
      (node (ref "IC5") (pin "3") (pinfunction "+IN_3") (pintype "input"))
      (node (ref "R14") (pin "1") (pinfunction "1_1") (pintype "passive"))
      (node (ref "R15") (pin "2") (pinfunction "2_2") (pintype "passive"))
    )
    (net (code "53") (name "Net-(IC5A--IN)") (class "Default")
      (node (ref "IC5") (pin "2") (pinfunction "-IN_2") (pintype "input"))
      (node (ref "R17") (pin "1") (pinfunction "1_1") (pintype "passive"))
      (node (ref "R18") (pin "2") (pinfunction "2_2") (pintype "passive"))
    )
    (net (code "54") (name "Net-(IC5A-OUT)") (class "Default")
      (node (ref "IC5") (pin "1") (pinfunction "OUT_1") (pintype "output"))
      (node (ref "R16") (pin "2") (pinfunction "2_2") (pintype "passive"))
      (node (ref "R18") (pin "1") (pinfunction "1_1") (pintype "passive"))
    )
    (net (code "55") (name "Net-(IC5B-+IN)") (class "Default")
      (node (ref "C6") (pin "2") (pinfunction "2_2") (pintype "passive"))
      (node (ref "IC5") (pin "5") (pinfunction "+IN_5") (pintype "input"))
      (node (ref "R16") (pin "1") (pinfunction "1_1") (pintype "passive"))
    )
    (net (code "56") (name "Net-(IC6A-+IN)") (class "Default")
      (node (ref "IC6") (pin "3") (pinfunction "+IN_3") (pintype "input"))
      (node (ref "R19") (pin "1") (pinfunction "1_1") (pintype "passive"))
      (node (ref "R20") (pin "2") (pinfunction "2_2") (pintype "passive"))
    )
    (net (code "57") (name "Net-(IC6A--IN)") (class "Default")
      (node (ref "IC6") (pin "2") (pinfunction "-IN_2") (pintype "input"))
      (node (ref "R22") (pin "1") (pinfunction "1_1") (pintype "passive"))
      (node (ref "R23") (pin "2") (pinfunction "2_2") (pintype "passive"))
    )
    (net (code "58") (name "Net-(IC6A-OUT)") (class "Default")
      (node (ref "IC6") (pin "1") (pinfunction "OUT_1") (pintype "output"))
      (node (ref "R21") (pin "2") (pinfunction "2_2") (pintype "passive"))
      (node (ref "R23") (pin "1") (pinfunction "1_1") (pintype "passive"))
    )
    (net (code "59") (name "Net-(IC6B-+IN)") (class "Default")
      (node (ref "C7") (pin "2") (pinfunction "2_2") (pintype "passive"))
      (node (ref "IC6") (pin "5") (pinfunction "+IN_5") (pintype "input"))
      (node (ref "R21") (pin "1") (pinfunction "1_1") (pintype "passive"))
    )
    (net (code "60") (name "Net-(IC7A-+IN)") (class "Default")
      (node (ref "IC7") (pin "3") (pinfunction "+IN_3") (pintype "input"))
      (node (ref "R24") (pin "2") (pinfunction "2_2") (pintype "passive"))
      (node (ref "R25") (pin "1") (pinfunction "1_1") (pintype "passive"))
    )
    (net (code "61") (name "Net-(IC7A--IN)") (class "Default")
      (node (ref "IC7") (pin "1") (pinfunction "OUT_1") (pintype "output"))
      (node (ref "IC7") (pin "2") (pinfunction "-IN_2") (pintype "input"))
    )
    (net (code "62") (name "Net-(IC7B-+IN)") (class "Default")
      (node (ref "IC7") (pin "5") (pinfunction "+IN_5") (pintype "input"))
      (node (ref "R25") (pin "2") (pinfunction "2_2") (pintype "passive"))
      (node (ref "R26") (pin "1") (pinfunction "1_1") (pintype "passive"))
    )
    (net (code "63") (name "Net-(IC7B--IN)") (class "Default")
      (node (ref "IC7") (pin "6") (pinfunction "-IN_6") (pintype "input"))
      (node (ref "R27") (pin "1") (pinfunction "1_1") (pintype "passive"))
      (node (ref "R28") (pin "2") (pinfunction "2_2") (pintype "passive"))
    )
    (net (code "64") (name "Net-(IC7B-OUT)") (class "Default")
      (node (ref "IC7") (pin "7") (pinfunction "OUT_7") (pintype "output"))
      (node (ref "R28") (pin "1") (pinfunction "1_1") (pintype "passive"))
      (node (ref "R29") (pin "2") (pinfunction "2_2") (pintype "passive"))
    )
    (net (code "65") (name "Net-(IC8A-+IN)") (class "Default")
      (node (ref "IC8") (pin "3") (pinfunction "+IN_3") (pintype "input"))
      (node (ref "IC9") (pin "3") (pinfunction "+IN_3") (pintype "input"))
      (node (ref "R29") (pin "1") (pinfunction "1_1") (pintype "passive"))
    )
    (net (code "66") (name "Net-(IC8A-OUT)") (class "Default")
      (node (ref "IC8") (pin "1") (pinfunction "OUT_1") (pintype "output"))
      (node (ref "U$6") (pin "1") (pinfunction "B_1") (pintype "passive"))
    )
    (net (code "67") (name "Net-(IC9A-OUT)") (class "Default")
      (node (ref "IC9") (pin "1") (pinfunction "OUT_1") (pintype "output"))
      (node (ref "U$7") (pin "1") (pinfunction "B_1") (pintype "passive"))
    )
    (net (code "68") (name "Net-(IC9B--IN)") (class "Default")
      (node (ref "IC9") (pin "6") (pinfunction "-IN_6") (pintype "input"))
      (node (ref "IC9") (pin "7") (pinfunction "OUT_7") (pintype "output"))
      (node (ref "U$11") (pin "2") (pinfunction "SHDN_2") (pintype "bidirectional"))
    )
    (net (code "69") (name "Net-(IC10A--IN)") (class "Default")
      (node (ref "IC10") (pin "2") (pinfunction "-IN_2") (pintype "input"))
      (node (ref "R30") (pin "1") (pinfunction "1_1") (pintype "passive"))
      (node (ref "R31") (pin "1") (pinfunction "1_1") (pintype "passive"))
      (node (ref "R32") (pin "2") (pinfunction "2_2") (pintype "passive"))
    )
    (net (code "70") (name "Net-(IC10A-OUT)") (class "Default")
      (node (ref "C8") (pin "1") (pinfunction "1_1") (pintype "passive"))
      (node (ref "IC10") (pin "1") (pinfunction "OUT_1") (pintype "output"))
      (node (ref "R33") (pin "2") (pinfunction "2_2") (pintype "passive"))
    )
    (net (code "71") (name "Net-(IC10B-+IN)") (class "Default")
      (node (ref "IC10") (pin "5") (pinfunction "+IN_5") (pintype "input"))
      (node (ref "R40") (pin "2") (pinfunction "2_2") (pintype "passive"))
      (node (ref "R45") (pin "2") (pinfunction "2_2") (pintype "passive"))
    )
    (net (code "72") (name "Net-(IC10B--IN)") (class "Default")
      (node (ref "IC10") (pin "6") (pinfunction "-IN_6") (pintype "input"))
      (node (ref "R41") (pin "2") (pinfunction "2_2") (pintype "passive"))
      (node (ref "R43") (pin "1") (pinfunction "1_1") (pintype "passive"))
    )
    (net (code "73") (name "Net-(IC10B-OUT)") (class "Default")
      (node (ref "IC10") (pin "7") (pinfunction "OUT_7") (pintype "output"))
      (node (ref "R30") (pin "2") (pinfunction "2_2") (pintype "passive"))
      (node (ref "R43") (pin "2") (pinfunction "2_2") (pintype "passive"))
    )
    (net (code "74") (name "Net-(IC11A--IN)") (class "Default")
      (node (ref "IC11") (pin "2") (pinfunction "-IN_2") (pintype "input"))
      (node (ref "R49") (pin "1") (pinfunction "1_1") (pintype "passive"))
      (node (ref "R50") (pin "2") (pinfunction "2_2") (pintype "passive"))
    )
    (net (code "75") (name "Net-(IC11A-OUT)") (class "Default")
      (node (ref "IC11") (pin "1") (pinfunction "OUT_1") (pintype "output"))
      (node (ref "R50") (pin "1") (pinfunction "1_1") (pintype "passive"))
      (node (ref "R51") (pin "2") (pinfunction "2_2") (pintype "passive"))
    )
    (net (code "76") (name "Net-(IC11B--IN)") (class "Default")
      (node (ref "IC11") (pin "6") (pinfunction "-IN_6") (pintype "input"))
      (node (ref "R51") (pin "1") (pinfunction "1_1") (pintype "passive"))
      (node (ref "R52") (pin "2") (pinfunction "2_2") (pintype "passive"))
      (node (ref "R53") (pin "2") (pinfunction "2_2") (pintype "passive"))
    )
    (net (code "77") (name "Net-(IC11B-OUT)") (class "Default")
      (node (ref "C16") (pin "1") (pinfunction "1_1") (pintype "passive"))
      (node (ref "IC11") (pin "7") (pinfunction "OUT_7") (pintype "output"))
      (node (ref "R54") (pin "2") (pinfunction "2_2") (pintype "passive"))
    )
    (net (code "78") (name "Net-(IC12A-+IN)") (class "Default")
      (node (ref "IC12") (pin "3") (pinfunction "+IN_3") (pintype "input"))
      (node (ref "R62") (pin "2") (pinfunction "2_2") (pintype "passive"))
      (node (ref "R63") (pin "2") (pinfunction "2_2") (pintype "passive"))
    )
    (net (code "79") (name "Net-(IC12A--IN)") (class "Default")
      (node (ref "IC12") (pin "2") (pinfunction "-IN_2") (pintype "input"))
      (node (ref "R58") (pin "1") (pinfunction "1_1") (pintype "passive"))
      (node (ref "R71") (pin "2") (pinfunction "2_2") (pintype "passive"))
    )
    (net (code "80") (name "Net-(IC12A-OUT)") (class "Default")
      (node (ref "IC12") (pin "1") (pinfunction "OUT_1") (pintype "output"))
      (node (ref "R53") (pin "1") (pinfunction "1_1") (pintype "passive"))
      (node (ref "R58") (pin "2") (pinfunction "2_2") (pintype "passive"))
    )
    (net (code "81") (name "Net-(LTC3411-ITH)") (class "Default")
      (node (ref "LTC3411") (pin "10") (pinfunction "ITH_10") (pintype "bidirectional"))
      (node (ref "R60") (pin "1") (pinfunction "1_1") (pintype "passive"))
    )
    (net (code "82") (name "Net-(LTC3411-PGOOD)") (class "Default")
      (node (ref "LTC3411") (pin "8") (pinfunction "PGOOD_8") (pintype "bidirectional"))
      (node (ref "R65") (pin "2") (pinfunction "2_2") (pintype "passive"))
    )
    (net (code "83") (name "Net-(LTC3411-SHDN{slash}RT)") (class "Default")
      (node (ref "LTC3411") (pin "1") (pinfunction "SHDN/RT_1") (pintype "bidirectional"))
      (node (ref "R59") (pin "1") (pinfunction "1_1") (pintype "passive"))
    )
    (net (code "84") (name "Net-(LTC3411-SW)") (class "Default")
      (node (ref "L2") (pin "1") (pinfunction "1_1") (pintype "passive"))
      (node (ref "LTC3411") (pin "4") (pinfunction "SW_4") (pintype "bidirectional"))
    )
    (net (code "85") (name "Net-(LTC3411-SYNC{slash}MODE)") (class "Default")
      (node (ref "LTC3411") (pin "2") (pinfunction "SYNC/MODE_2") (pintype "bidirectional"))
      (node (ref "R61") (pin "2") (pinfunction "2_2") (pintype "passive"))
      (node (ref "R64") (pin "1") (pinfunction "1_1") (pintype "passive"))
    )
    (net (code "86") (name "Net-(LTC3411-VFB)") (class "Default")
      (node (ref "LTC3411") (pin "9") (pinfunction "VFB_9") (pintype "bidirectional"))
      (node (ref "R54") (pin "1") (pinfunction "1_1") (pintype "passive"))
      (node (ref "R55") (pin "2") (pinfunction "2_2") (pintype "passive"))
      (node (ref "R56") (pin "1") (pinfunction "1_1") (pintype "passive"))
    )
    (net (code "87") (name "Net-(R48-Pad2)") (class "Default")
      (node (ref "R48") (pin "2") (pinfunction "2_2") (pintype "passive"))
      (node (ref "U$1") (pin "63") (pinfunction "63_63") (pintype "bidirectional"))
    )
    (net (code "88") (name "Net-(U$2-OUT)") (class "Default")
      (node (ref "R9") (pin "2") (pinfunction "2_2") (pintype "passive"))
      (node (ref "U$2") (pin "4") (pinfunction "OUT_4") (pintype "bidirectional"))
    )
    (net (code "89") (name "Net-(U$3-OUT)") (class "Default")
      (node (ref "R7") (pin "2") (pinfunction "2_2") (pintype "passive"))
      (node (ref "U$3") (pin "4") (pinfunction "OUT_4") (pintype "bidirectional"))
    )
    (net (code "90") (name "Net-(U$4-OUT)") (class "Default")
      (node (ref "R11") (pin "2") (pinfunction "2_2") (pintype "passive"))
      (node (ref "U$4") (pin "4") (pinfunction "OUT_4") (pintype "bidirectional"))
    )
    (net (code "91") (name "Net-(U$5-OUT)") (class "Default")
      (node (ref "R13") (pin "2") (pinfunction "2_2") (pintype "passive"))
      (node (ref "U$5") (pin "4") (pinfunction "OUT_4") (pintype "bidirectional"))
    )
    (net (code "92") (name "Net-(U$8-D)") (class "Default")
      (node (ref "R59") (pin "2") (pinfunction "2_2") (pintype "passive"))
      (node (ref "R70") (pin "2") (pinfunction "2_2") (pintype "passive"))
      (node (ref "U$8") (pin "3") (pinfunction "D_3") (pintype "bidirectional"))
    )
    (net (code "93") (name "Net-(U$11-BURST)") (class "Default")
      (node (ref "C10") (pin "2") (pinfunction "2_2") (pintype "passive"))
      (node (ref "R36") (pin "2") (pinfunction "2_2") (pintype "passive"))
      (node (ref "R44") (pin "1") (pinfunction "1_1") (pintype "passive"))
      (node (ref "U$11") (pin "9") (pinfunction "BURST_9") (pintype "bidirectional"))
    )
    (net (code "94") (name "Net-(U$11-FB)") (class "Default")
      (node (ref "R33") (pin "1") (pinfunction "1_1") (pintype "passive"))
      (node (ref "R34") (pin "1") (pinfunction "1_1") (pintype "passive"))
      (node (ref "R35") (pin "2") (pinfunction "2_2") (pintype "passive"))
      (node (ref "U$11") (pin "1") (pinfunction "FB_1") (pintype "bidirectional"))
    )
    (net (code "95") (name "Net-(U$11-ILIM)") (class "Default")
      (node (ref "R42") (pin "1") (pinfunction "1_1") (pintype "passive"))
      (node (ref "U$11") (pin "8") (pinfunction "ILIM_8") (pintype "bidirectional"))
    )
    (net (code "96") (name "Net-(U$11-RT)") (class "Default")
      (node (ref "R37") (pin "1") (pinfunction "1_1") (pintype "passive"))
      (node (ref "U$11") (pin "5") (pinfunction "RT_5") (pintype "bidirectional"))
    )
    (net (code "97") (name "Net-(U$11-SS)") (class "Default")
      (node (ref "C11") (pin "2") (pinfunction "2_2") (pintype "passive"))
      (node (ref "U$11") (pin "6") (pinfunction "SS_6") (pintype "bidirectional"))
    )
    (net (code "98") (name "Net-(U$11-SW1)") (class "Default")
      (node (ref "L1") (pin "2") (pinfunction "2_2") (pintype "passive"))
      (node (ref "U$11") (pin "14") (pinfunction "SW1_14") (pintype "bidirectional"))
      (node (ref "U$11") (pin "15") (pinfunction "SW2_15") (pintype "bidirectional"))
      (node (ref "U$11") (pin "16") (pinfunction "SW3_16") (pintype "bidirectional"))
    )
    (net (code "99") (name "Net-(U$11-VC)") (class "Default")
      (node (ref "R38") (pin "1") (pinfunction "1_1") (pintype "passive"))
      (node (ref "U$11") (pin "24") (pinfunction "VC_24") (pintype "bidirectional"))
    )
    (net (code "100") (name "Net-(U$11-VOUT1)") (class "Default")
      (node (ref "C9") (pin "+") (pinfunction "+_+") (pintype "passive"))
      (node (ref "R35") (pin "1") (pinfunction "1_1") (pintype "passive"))
      (node (ref "R36") (pin "1") (pinfunction "1_1") (pintype "passive"))
      (node (ref "R39") (pin "2") (pinfunction "2_2") (pintype "passive"))
      (node (ref "R41") (pin "1") (pinfunction "1_1") (pintype "passive"))
      (node (ref "U$11") (pin "17") (pinfunction "VOUT1_17") (pintype "bidirectional"))
      (node (ref "U$11") (pin "18") (pinfunction "VOUTS_18") (pintype "bidirectional"))
      (node (ref "U$11") (pin "19") (pinfunction "VOUT2_19") (pintype "bidirectional"))
      (node (ref "U$11") (pin "20") (pinfunction "VOUT3_20") (pintype "bidirectional"))
    )
    (net (code "101") (name "Net-(U$13-D)") (class "Default")
      (node (ref "R81") (pin "2") (pinfunction "2_2") (pintype "passive"))
      (node (ref "U$13") (pin "3") (pinfunction "D_3") (pintype "bidirectional"))
      (node (ref "U$16") (pin "4") (pinfunction "EN_4") (pintype "bidirectional"))
    )
    (net (code "102") (name "Net-(U$14-D)") (class "Default")
      (node (ref "R79") (pin "2") (pinfunction "2_2") (pintype "passive"))
      (node (ref "U$14") (pin "3") (pinfunction "D_3") (pintype "bidirectional"))
      (node (ref "U$18") (pin "4") (pinfunction "EN_4") (pintype "bidirectional"))
    )
    (net (code "103") (name "Net-(U$15-D)") (class "Default")
      (node (ref "R80") (pin "2") (pinfunction "2_2") (pintype "passive"))
      (node (ref "U$15") (pin "3") (pinfunction "D_3") (pintype "bidirectional"))
      (node (ref "U$17") (pin "4") (pinfunction "EN_4") (pintype "bidirectional"))
    )
    (net (code "104") (name "VCC") (class "Default")
      (node (ref "C12") (pin "+") (pinfunction "+_+") (pintype "passive"))
      (node (ref "C21") (pin "1") (pinfunction "1_1") (pintype "passive"))
      (node (ref "C27") (pin "2") (pinfunction "2_2") (pintype "passive"))
      (node (ref "C_IC10") (pin "2") (pinfunction "2_2") (pintype "passive"))
      (node (ref "C_IC11") (pin "2") (pinfunction "2_2") (pintype "passive"))
      (node (ref "C_IC12") (pin "2") (pinfunction "2_2") (pintype "passive"))
      (node (ref "C_IC2") (pin "2") (pinfunction "2_2") (pintype "passive"))
      (node (ref "C_IC3") (pin "2") (pinfunction "2_2") (pintype "passive"))
      (node (ref "C_IC4") (pin "2") (pinfunction "2_2") (pintype "passive"))
      (node (ref "C_IC5") (pin "2") (pinfunction "2_2") (pintype "passive"))
      (node (ref "C_IC6") (pin "2") (pinfunction "2_2") (pintype "passive"))
      (node (ref "C_IC7") (pin "2") (pinfunction "2_2") (pintype "passive"))
      (node (ref "C_IC8") (pin "2") (pinfunction "2_2") (pintype "passive"))
      (node (ref "C_IC9") (pin "2") (pinfunction "2_2") (pintype "passive"))
      (node (ref "FERRITE_BEAD") (pin "1") (pinfunction "1_1") (pintype "passive"))
      (node (ref "IC10") (pin "8") (pinfunction "V+_8") (pintype "power_in"))
      (node (ref "IC11") (pin "8") (pinfunction "V+_8") (pintype "power_in"))
      (node (ref "IC12") (pin "8") (pinfunction "V+_8") (pintype "power_in"))
      (node (ref "IC2") (pin "8") (pinfunction "V+_8") (pintype "power_in"))
      (node (ref "IC3") (pin "8") (pinfunction "V+_8") (pintype "power_in"))
      (node (ref "IC4") (pin "8") (pinfunction "V+_8") (pintype "power_in"))
      (node (ref "IC5") (pin "8") (pinfunction "V+_8") (pintype "power_in"))
      (node (ref "IC6") (pin "8") (pinfunction "V+_8") (pintype "power_in"))
      (node (ref "IC7") (pin "8") (pinfunction "V+_8") (pintype "power_in"))
      (node (ref "IC8") (pin "8") (pinfunction "V+_8") (pintype "power_in"))
      (node (ref "IC9") (pin "8") (pinfunction "V+_8") (pintype "power_in"))
      (node (ref "L1") (pin "1") (pinfunction "1_1") (pintype "passive"))
      (node (ref "R1") (pin "2") (pinfunction "2_2") (pintype "passive"))
      (node (ref "R14") (pin "2") (pinfunction "2_2") (pintype "passive"))
      (node (ref "R24") (pin "1") (pinfunction "1_1") (pintype "passive"))
      (node (ref "R57") (pin "1") (pinfunction "1_1") (pintype "passive"))
      (node (ref "R6") (pin "1") (pinfunction "1_1") (pintype "passive"))
      (node (ref "R63") (pin "1") (pinfunction "1_1") (pintype "passive"))
      (node (ref "R79") (pin "1") (pinfunction "1_1") (pintype "passive"))
      (node (ref "R8") (pin "2") (pinfunction "2_2") (pintype "passive"))
      (node (ref "R80") (pin "1") (pinfunction "1_1") (pintype "passive"))
      (node (ref "R81") (pin "1") (pinfunction "1_1") (pintype "passive"))
      (node (ref "U$1") (pin "11") (pinfunction "11_11") (pintype "power_in"))
      (node (ref "U$11") (pin "21") (pinfunction "VIN_21") (pintype "bidirectional"))
      (node (ref "U$19") (pin "3") (pinfunction "VIN_3") (pintype "bidirectional"))
      (node (ref "U$2") (pin "1") (pinfunction "VCC_1") (pintype "bidirectional"))
      (node (ref "U$2") (pin "6") (pinfunction "RS-_6") (pintype "bidirectional"))
      (node (ref "U$3") (pin "1") (pinfunction "VCC_1") (pintype "bidirectional"))
      (node (ref "U$3") (pin "8") (pinfunction "RS+_8") (pintype "bidirectional"))
      (node (ref "U$4") (pin "1") (pinfunction "VCC_1") (pintype "bidirectional"))
      (node (ref "U$5") (pin "1") (pinfunction "VCC_1") (pintype "bidirectional"))
      (node (ref "U$6") (pin "2") (pinfunction "C_2") (pintype "passive"))
      (node (ref "U$7") (pin "2") (pinfunction "C_2") (pintype "passive"))
    )
    (net (code "105") (name "unconnected-(IC8B-OUT-Pad7)") (class "Default")
      (node (ref "IC8") (pin "7") (pinfunction "OUT_7") (pintype "output"))
    )
    (net (code "106") (name "unconnected-(U$1-Pad3)") (class "Default")
      (node (ref "U$1") (pin "3") (pinfunction "3_3") (pintype "bidirectional"))
    )
    (net (code "107") (name "unconnected-(U$1-Pad4)") (class "Default")
      (node (ref "U$1") (pin "4") (pinfunction "4_4") (pintype "bidirectional"))
    )
    (net (code "108") (name "unconnected-(U$1-Pad9)") (class "Default")
      (node (ref "U$1") (pin "9") (pinfunction "9_9") (pintype "bidirectional"))
    )
    (net (code "109") (name "unconnected-(U$1-Pad10)") (class "Default")
      (node (ref "U$1") (pin "10") (pinfunction "10_10") (pintype "bidirectional"))
    )
    (net (code "110") (name "unconnected-(U$1-Pad15)") (class "Default")
      (node (ref "U$1") (pin "15") (pinfunction "15_15") (pintype "bidirectional"))
    )
    (net (code "111") (name "unconnected-(U$1-Pad16)") (class "Default")
      (node (ref "U$1") (pin "16") (pinfunction "16_16") (pintype "bidirectional"))
    )
    (net (code "112") (name "unconnected-(U$1-Pad17)") (class "Default")
      (node (ref "U$1") (pin "17") (pinfunction "17_17") (pintype "bidirectional"))
    )
    (net (code "113") (name "unconnected-(U$1-Pad21)") (class "Default")
      (node (ref "U$1") (pin "21") (pinfunction "21_21") (pintype "bidirectional"))
    )
    (net (code "114") (name "unconnected-(U$1-Pad22)") (class "Default")
      (node (ref "U$1") (pin "22") (pinfunction "22_22") (pintype "bidirectional"))
    )
    (net (code "115") (name "unconnected-(U$1-Pad23)") (class "Default")
      (node (ref "U$1") (pin "23") (pinfunction "23_23") (pintype "bidirectional"))
    )
    (net (code "116") (name "unconnected-(U$1-Pad24)") (class "Default")
      (node (ref "U$1") (pin "24") (pinfunction "24_24") (pintype "bidirectional"))
    )
    (net (code "117") (name "unconnected-(U$1-Pad25)") (class "Default")
      (node (ref "U$1") (pin "25") (pinfunction "25_25") (pintype "bidirectional"))
    )
    (net (code "118") (name "unconnected-(U$1-Pad26)") (class "Default")
      (node (ref "U$1") (pin "26") (pinfunction "26_26") (pintype "bidirectional"))
    )
    (net (code "119") (name "unconnected-(U$1-Pad27)") (class "Default")
      (node (ref "U$1") (pin "27") (pinfunction "27_27") (pintype "bidirectional"))
    )
    (net (code "120") (name "unconnected-(U$1-Pad28)") (class "Default")
      (node (ref "U$1") (pin "28") (pinfunction "28_28") (pintype "bidirectional"))
    )
    (net (code "121") (name "unconnected-(U$1-Pad30)") (class "Default")
      (node (ref "U$1") (pin "30") (pinfunction "30_30") (pintype "bidirectional"))
    )
    (net (code "122") (name "unconnected-(U$1-Pad34)") (class "Default")
      (node (ref "U$1") (pin "34") (pinfunction "34_34") (pintype "bidirectional"))
    )
    (net (code "123") (name "unconnected-(U$1-Pad35)") (class "Default")
      (node (ref "U$1") (pin "35") (pinfunction "35_35") (pintype "bidirectional"))
    )
    (net (code "124") (name "unconnected-(U$1-Pad36)") (class "Default")
      (node (ref "U$1") (pin "36") (pinfunction "36_36") (pintype "bidirectional"))
    )
    (net (code "125") (name "unconnected-(U$1-Pad37)") (class "Default")
      (node (ref "U$1") (pin "37") (pinfunction "37_37") (pintype "bidirectional"))
    )
    (net (code "126") (name "unconnected-(U$1-Pad38)") (class "Default")
      (node (ref "U$1") (pin "38") (pinfunction "38_38") (pintype "bidirectional"))
    )
    (net (code "127") (name "unconnected-(U$1-Pad39)") (class "Default")
      (node (ref "U$1") (pin "39") (pinfunction "39_39") (pintype "bidirectional"))
    )
    (net (code "128") (name "unconnected-(U$1-Pad40)") (class "Default")
      (node (ref "U$1") (pin "40") (pinfunction "40_40") (pintype "bidirectional"))
    )
    (net (code "129") (name "unconnected-(U$1-Pad41)") (class "Default")
      (node (ref "U$1") (pin "41") (pinfunction "41_41") (pintype "bidirectional"))
    )
    (net (code "130") (name "unconnected-(U$1-Pad42)") (class "Default")
      (node (ref "U$1") (pin "42") (pinfunction "42_42") (pintype "bidirectional"))
    )
    (net (code "131") (name "unconnected-(U$1-Pad43)") (class "Default")
      (node (ref "U$1") (pin "43") (pinfunction "43_43") (pintype "bidirectional"))
    )
    (net (code "132") (name "unconnected-(U$1-Pad44)") (class "Default")
      (node (ref "U$1") (pin "44") (pinfunction "44_44") (pintype "bidirectional"))
    )
    (net (code "133") (name "unconnected-(U$1-Pad48)") (class "Default")
      (node (ref "U$1") (pin "48") (pinfunction "48_48") (pintype "bidirectional"))
    )
    (net (code "134") (name "unconnected-(U$1-Pad51)") (class "Default")
      (node (ref "U$1") (pin "51") (pinfunction "51_51") (pintype "bidirectional"))
    )
    (net (code "135") (name "unconnected-(U$1-Pad52)") (class "Default")
      (node (ref "U$1") (pin "52") (pinfunction "52_52") (pintype "bidirectional"))
    )
    (net (code "136") (name "unconnected-(U$1-Pad53)") (class "Default")
      (node (ref "U$1") (pin "53") (pinfunction "53_53") (pintype "bidirectional"))
    )
    (net (code "137") (name "unconnected-(U$1-Pad54)") (class "Default")
      (node (ref "U$1") (pin "54") (pinfunction "54_54") (pintype "bidirectional"))
    )
    (net (code "138") (name "unconnected-(U$1-Pad55)") (class "Default")
      (node (ref "U$1") (pin "55") (pinfunction "55_55") (pintype "bidirectional"))
    )
    (net (code "139") (name "unconnected-(U$1-Pad56)") (class "Default")
      (node (ref "U$1") (pin "56") (pinfunction "56_56") (pintype "bidirectional"))
    )
    (net (code "140") (name "unconnected-(U$1-Pad57)") (class "Default")
      (node (ref "U$1") (pin "57") (pinfunction "57_57") (pintype "bidirectional"))
    )
    (net (code "141") (name "unconnected-(U$1-Pad58)") (class "Default")
      (node (ref "U$1") (pin "58") (pinfunction "58_58") (pintype "bidirectional"))
    )
    (net (code "142") (name "unconnected-(U$1-Pad59)") (class "Default")
      (node (ref "U$1") (pin "59") (pinfunction "59_59") (pintype "bidirectional"))
    )
    (net (code "143") (name "unconnected-(U$1-Pad60)") (class "Default")
      (node (ref "U$1") (pin "60") (pinfunction "60_60") (pintype "bidirectional"))
    )
    (net (code "144") (name "unconnected-(U$1-Pad62)") (class "Default")
      (node (ref "U$1") (pin "62") (pinfunction "62_62") (pintype "bidirectional"))
    )
    (net (code "145") (name "unconnected-(U$1-Pad64)") (class "Default")
      (node (ref "U$1") (pin "64") (pinfunction "64_64") (pintype "bidirectional"))
    )
    (net (code "146") (name "unconnected-(U$1-Pad69)") (class "Default")
      (node (ref "U$1") (pin "69") (pinfunction "69_69") (pintype "bidirectional"))
    )
    (net (code "147") (name "unconnected-(U$1-Pad70)") (class "Default")
      (node (ref "U$1") (pin "70") (pinfunction "70_70") (pintype "bidirectional"))
    )
    (net (code "148") (name "unconnected-(U$1-Pad72)") (class "Default")
      (node (ref "U$1") (pin "72") (pinfunction "72_72") (pintype "bidirectional"))
    )
    (net (code "149") (name "unconnected-(U$1-Pad73)") (class "Default")
      (node (ref "U$1") (pin "73") (pinfunction "73_73") (pintype "bidirectional"))
    )
    (net (code "150") (name "unconnected-(U$1-Pad74)") (class "Default")
      (node (ref "U$1") (pin "74") (pinfunction "74_74") (pintype "bidirectional"))
    )
    (net (code "151") (name "unconnected-(U$1-Pad75)") (class "Default")
      (node (ref "U$1") (pin "75") (pinfunction "75_75") (pintype "bidirectional"))
    )
    (net (code "152") (name "unconnected-(U$2-NC-Pad2)") (class "Default")
      (node (ref "U$2") (pin "2") (pinfunction "NC_2") (pintype "bidirectional"))
    )
    (net (code "153") (name "unconnected-(U$2-NC1-Pad5)") (class "Default")
      (node (ref "U$2") (pin "5") (pinfunction "NC1_5") (pintype "bidirectional"))
    )
    (net (code "154") (name "unconnected-(U$2-NC2-Pad7)") (class "Default")
      (node (ref "U$2") (pin "7") (pinfunction "NC2_7") (pintype "bidirectional"))
    )
    (net (code "155") (name "unconnected-(U$3-NC-Pad2)") (class "Default")
      (node (ref "U$3") (pin "2") (pinfunction "NC_2") (pintype "bidirectional"))
    )
    (net (code "156") (name "unconnected-(U$3-NC1-Pad5)") (class "Default")
      (node (ref "U$3") (pin "5") (pinfunction "NC1_5") (pintype "bidirectional"))
    )
    (net (code "157") (name "unconnected-(U$3-NC2-Pad7)") (class "Default")
      (node (ref "U$3") (pin "7") (pinfunction "NC2_7") (pintype "bidirectional"))
    )
    (net (code "158") (name "unconnected-(U$4-NC-Pad2)") (class "Default")
      (node (ref "U$4") (pin "2") (pinfunction "NC_2") (pintype "bidirectional"))
    )
    (net (code "159") (name "unconnected-(U$4-NC1-Pad5)") (class "Default")
      (node (ref "U$4") (pin "5") (pinfunction "NC1_5") (pintype "bidirectional"))
    )
    (net (code "160") (name "unconnected-(U$4-NC2-Pad7)") (class "Default")
      (node (ref "U$4") (pin "7") (pinfunction "NC2_7") (pintype "bidirectional"))
    )
    (net (code "161") (name "unconnected-(U$5-NC-Pad2)") (class "Default")
      (node (ref "U$5") (pin "2") (pinfunction "NC_2") (pintype "bidirectional"))
    )
    (net (code "162") (name "unconnected-(U$5-NC1-Pad5)") (class "Default")
      (node (ref "U$5") (pin "5") (pinfunction "NC1_5") (pintype "bidirectional"))
    )
    (net (code "163") (name "unconnected-(U$5-NC2-Pad7)") (class "Default")
      (node (ref "U$5") (pin "7") (pinfunction "NC2_7") (pintype "bidirectional"))
    )
    (net (code "164") (name "unconnected-(U$11-LBO-Pad22)") (class "Default")
      (node (ref "U$11") (pin "22") (pinfunction "LBO_22") (pintype "bidirectional"))
    )
    (net (code "165") (name "unconnected-(U$11-VREF-Pad3)") (class "Default")
      (node (ref "U$11") (pin "3") (pinfunction "VREF_3") (pintype "bidirectional"))
    )
    (net (code "166") (name "unconnected-(U$16-OC-Pad5)") (class "Default")
      (node (ref "U$16") (pin "5") (pinfunction "OC_5") (pintype "bidirectional"))
    )
    (net (code "167") (name "unconnected-(U$17-OC-Pad5)") (class "Default")
      (node (ref "U$17") (pin "5") (pinfunction "OC_5") (pintype "bidirectional"))
    )
    (net (code "168") (name "unconnected-(U$18-OC-Pad5)") (class "Default")
      (node (ref "U$18") (pin "5") (pinfunction "OC_5") (pintype "bidirectional"))
    )
    (net (code "169") (name "unconnected-(U$19-NC1-Pad1)") (class "Default")
      (node (ref "U$19") (pin "1") (pinfunction "NC1_1") (pintype "bidirectional"))
    )
    (net (code "170") (name "unconnected-(U$19-NC2-Pad5)") (class "Default")
      (node (ref "U$19") (pin "5") (pinfunction "NC2_5") (pintype "bidirectional"))
    )
    (net (code "171") (name "unconnected-(U$19-NC3-Pad6)") (class "Default")
      (node (ref "U$19") (pin "6") (pinfunction "NC3_6") (pintype "bidirectional"))
    )
  )
)
